# M865B.net
KiCad netlist of a schematic drawn in EAGLE
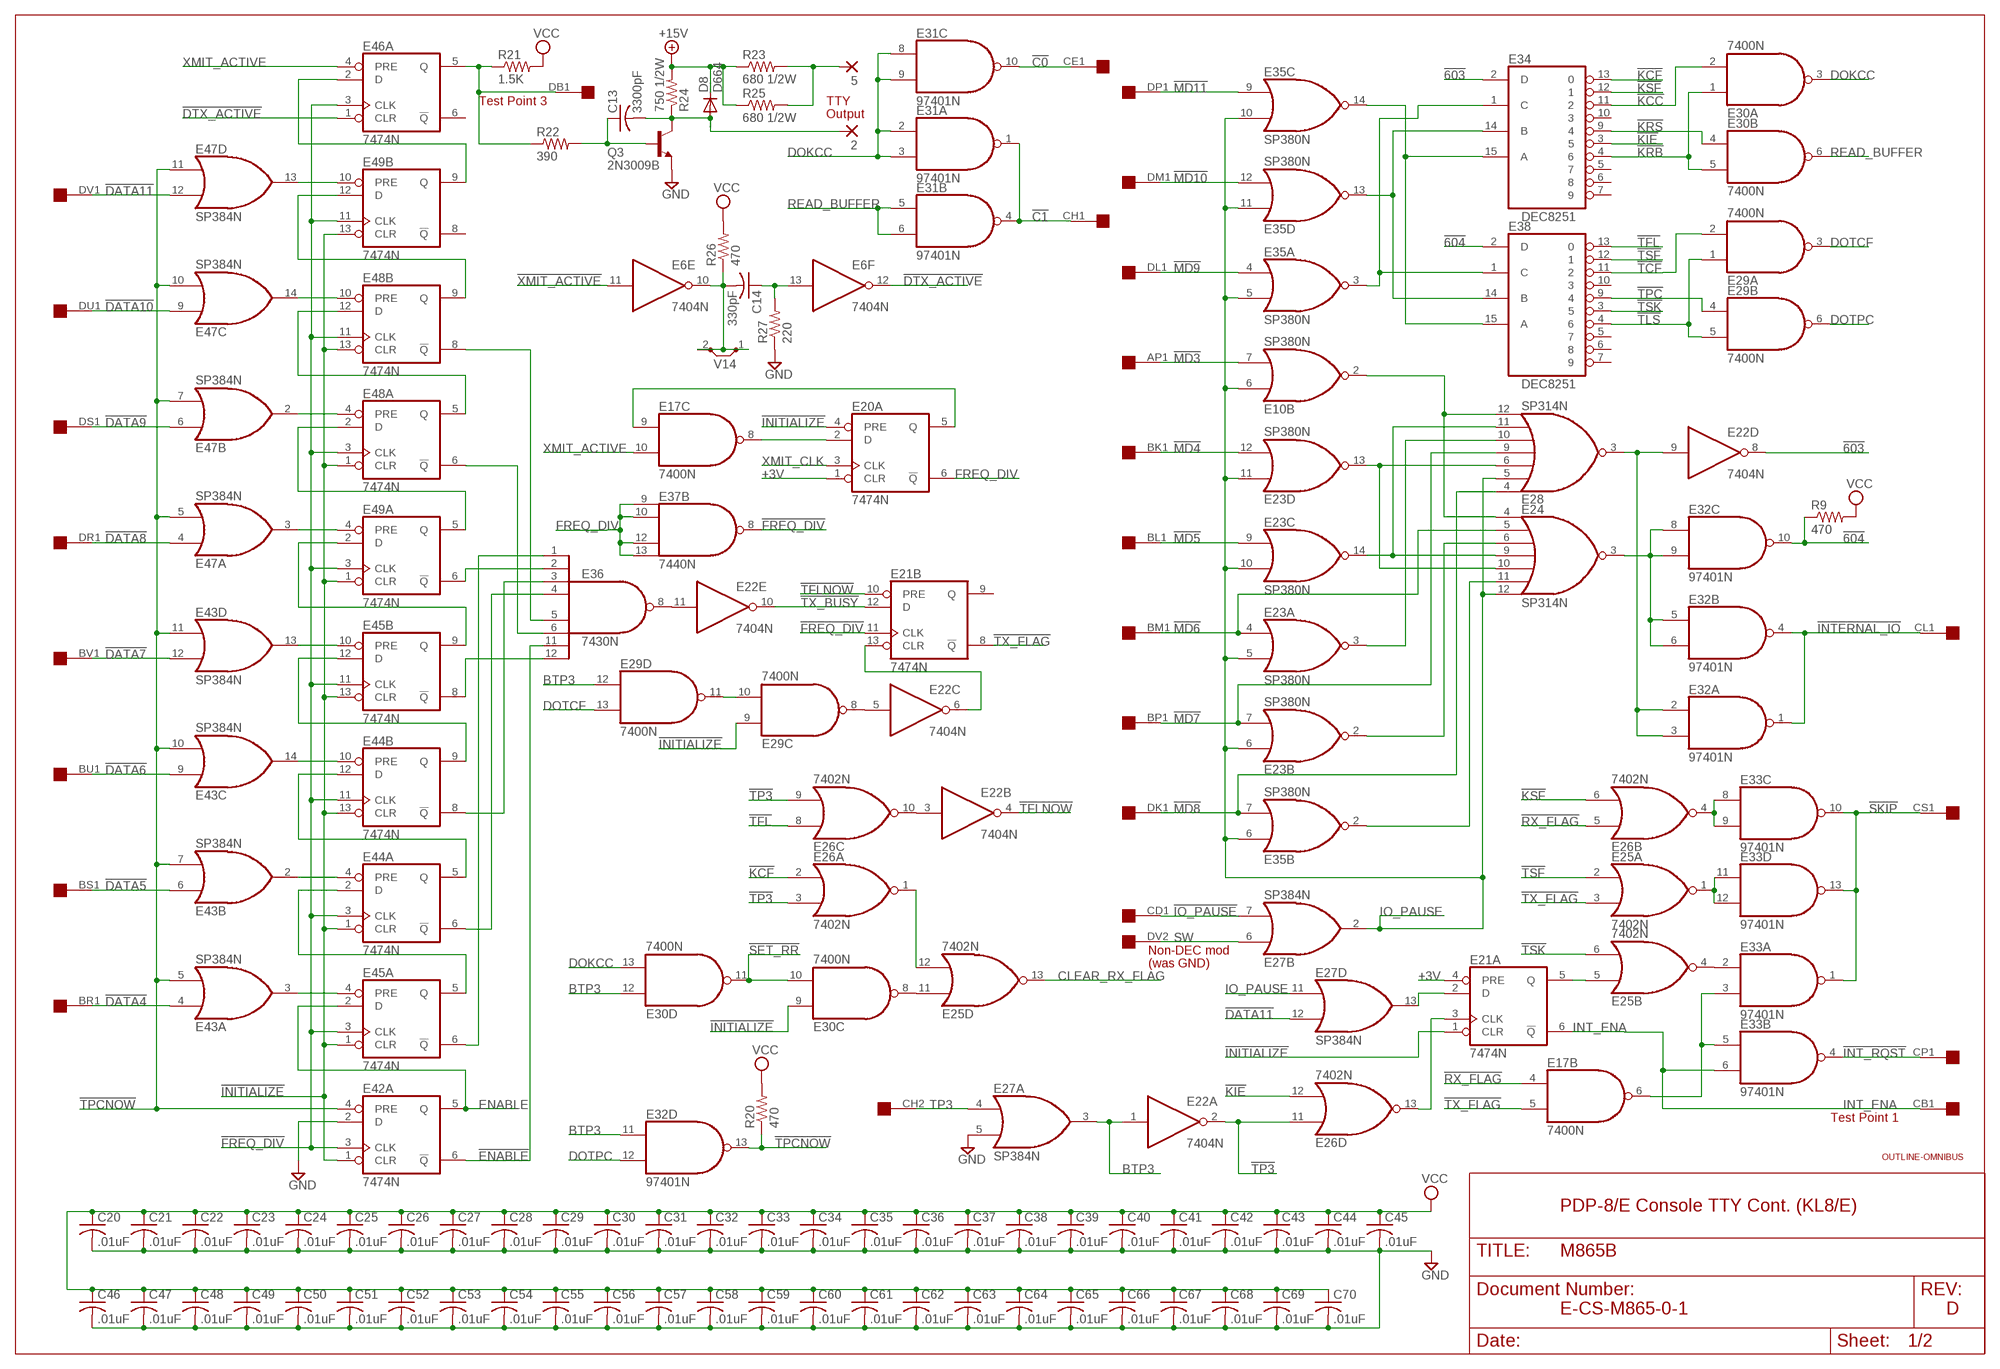
[diagram p0: schematic, sheet 1]
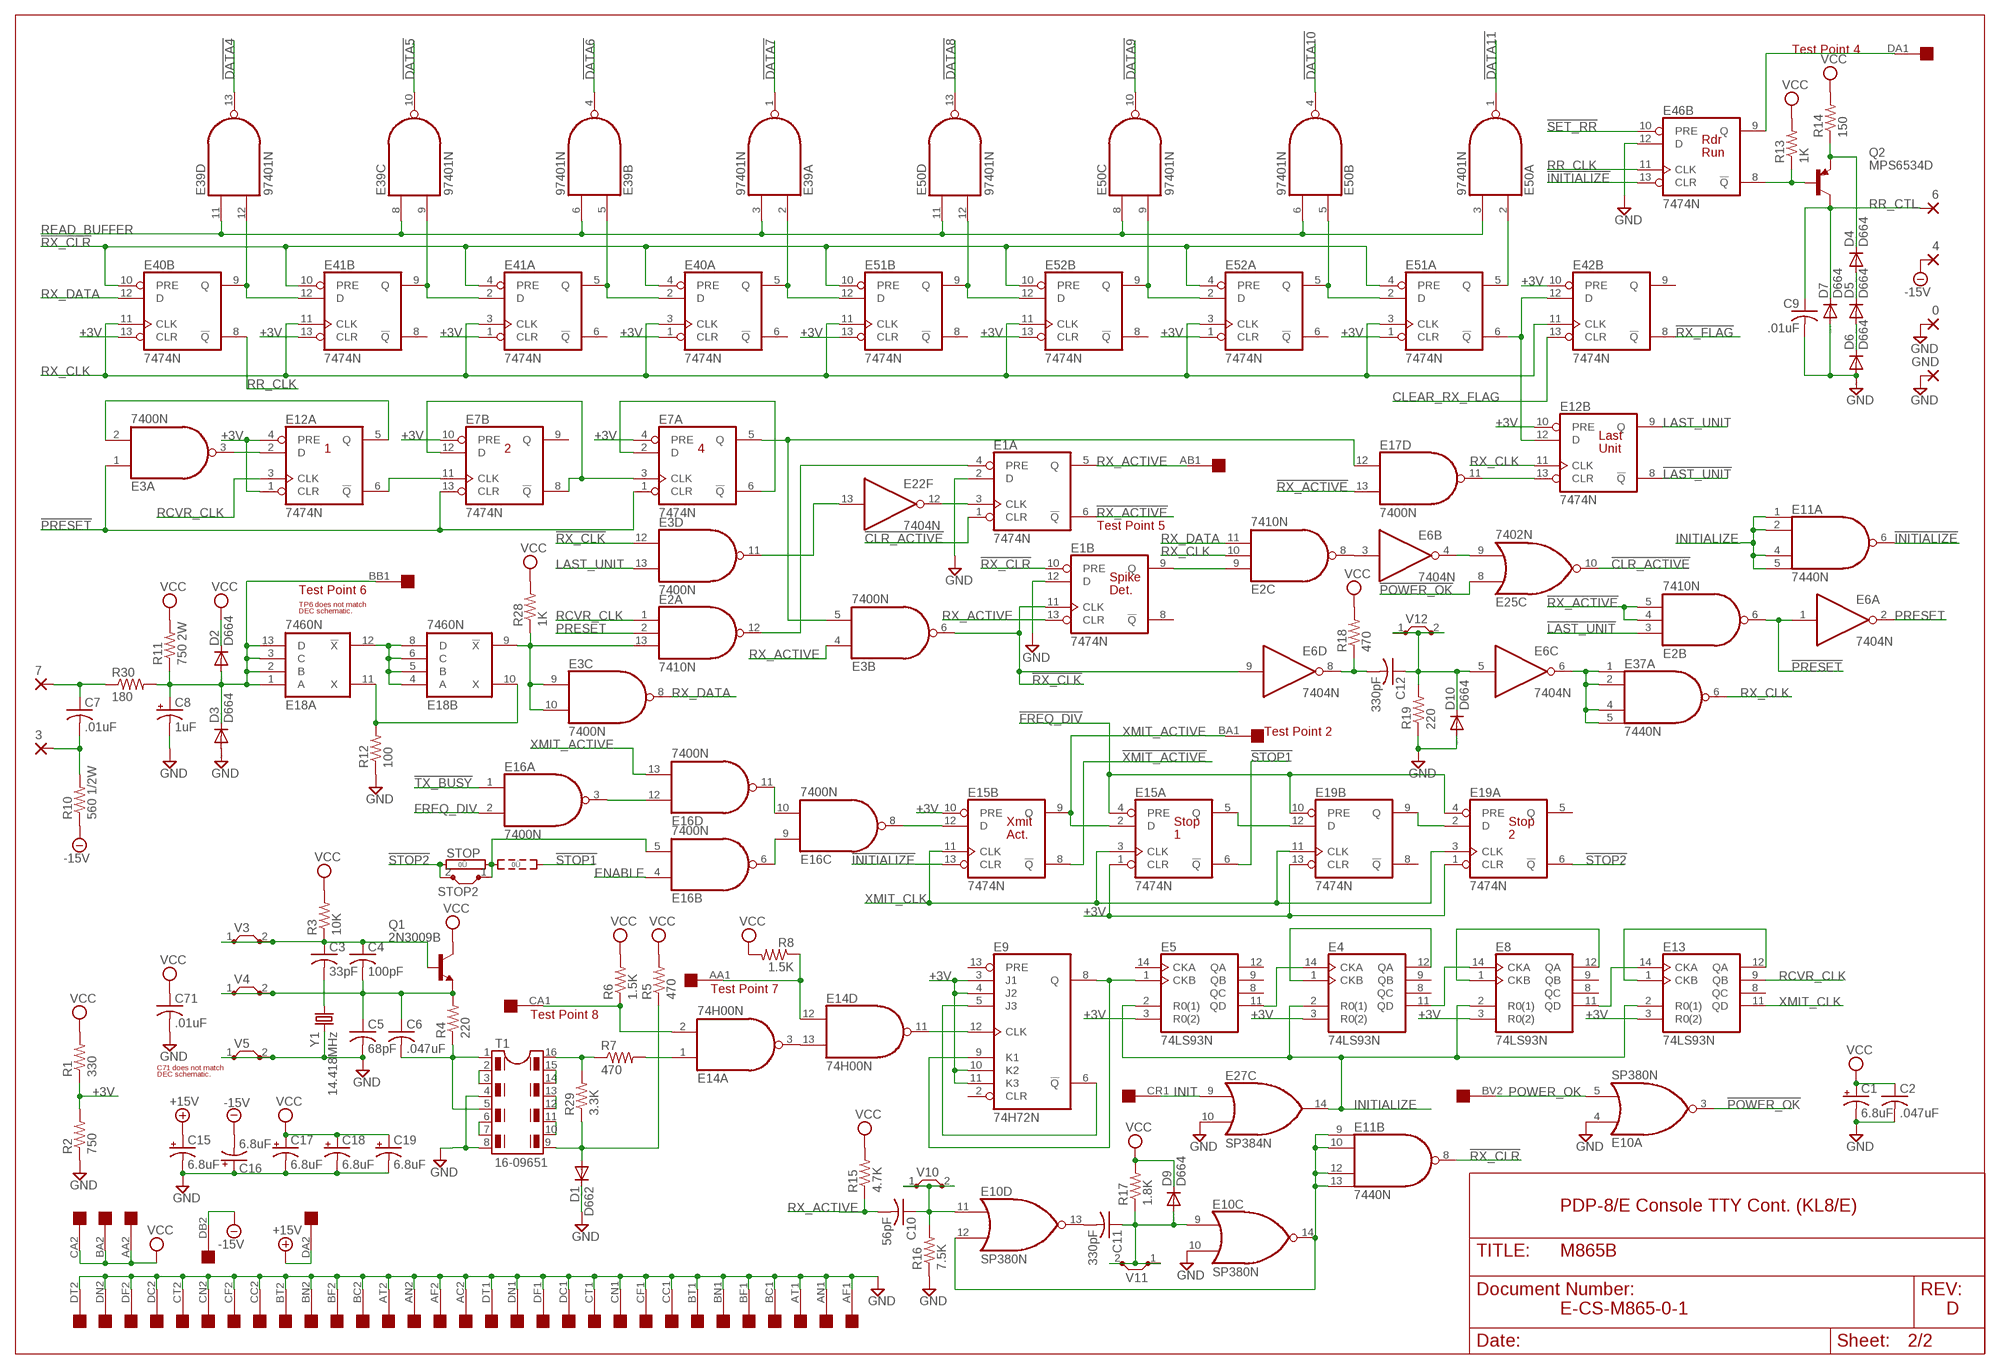
[diagram p1: schematic, sheet 2]

(export (version "E")
  (design (tool "Eeschema 10.0.6"))
  (components
    (comp (ref "0")
      (value "2,15/1,0")
      (footprint "eagle-import:2,15_1,0")
      (libsource (lib "eagle-import") (part "2,15/1,0"))
    )
    (comp (ref "3")
      (value "2,15/1,0")
      (footprint "eagle-import:2,15_1,0")
      (libsource (lib "eagle-import") (part "2,15/1,0"))
    )
    (comp (ref "4")
      (value "2,15/1,0")
      (footprint "eagle-import:2,15_1,0")
      (libsource (lib "eagle-import") (part "2,15/1,0"))
    )
    (comp (ref "6")
      (value "2,15/1,0")
      (footprint "eagle-import:2,15_1,0")
      (libsource (lib "eagle-import") (part "2,15/1,0"))
    )
    (comp (ref "7")
      (value "2,15/1,0")
      (footprint "eagle-import:2,15_1,0")
      (libsource (lib "eagle-import") (part "2,15/1,0"))
    )
    (comp (ref "C1")
      (value "6.8uF")
      (footprint "eagle-import:E12-8")
      (libsource (lib "eagle-import") (part "CPOL-USE20-8AXIAL"))
    )
    (comp (ref "C2")
      (value ".047uF")
      (footprint "eagle-import:C075-032X103")
      (libsource (lib "eagle-import") (part "C-US075-032X103"))
    )
    (comp (ref "C3")
      (value "33pF")
      (footprint "eagle-import:C050-025X075")
      (libsource (lib "eagle-import") (part "C-US050-025X075"))
    )
    (comp (ref "C4")
      (value "100pF")
      (footprint "eagle-import:C050-025X075")
      (libsource (lib "eagle-import") (part "C-US050-025X075"))
    )
    (comp (ref "C5")
      (value "68pF")
      (footprint "eagle-import:C050-025X075")
      (libsource (lib "eagle-import") (part "C-US050-025X075"))
    )
    (comp (ref "C6")
      (value ".047uF")
      (footprint "eagle-import:C075-032X103")
      (libsource (lib "eagle-import") (part "C-US075-032X103"))
    )
    (comp (ref "C7")
      (value ".01uF")
      (footprint "eagle-import:C050-025X075")
      (libsource (lib "eagle-import") (part "C-US050-025X075"))
    )
    (comp (ref "C8")
      (value "1uF")
      (footprint "eagle-import:E15-5")
      (libsource (lib "eagle-import") (part "CPOL-USE15-5AXIAL"))
    )
    (comp (ref "C9")
      (value ".01uF")
      (footprint "eagle-import:C050-025X075")
      (libsource (lib "eagle-import") (part "C-US050-025X075"))
    )
    (comp (ref "C10")
      (value "56pF")
      (footprint "eagle-import:C050-025X075")
      (libsource (lib "eagle-import") (part "C-US050-025X075"))
    )
    (comp (ref "C11")
      (value "330pF")
      (footprint "eagle-import:C050-025X075")
      (libsource (lib "eagle-import") (part "C-US050-025X075"))
    )
    (comp (ref "C12")
      (value "330pF")
      (footprint "eagle-import:C050-025X075")
      (libsource (lib "eagle-import") (part "C-US050-025X075"))
    )
    (comp (ref "C15")
      (value "6.8uF")
      (footprint "eagle-import:E12-8")
      (libsource (lib "eagle-import") (part "CPOL-USE20-8AXIAL"))
    )
    (comp (ref "C16")
      (value "6.8uF")
      (footprint "eagle-import:E12-8")
      (libsource (lib "eagle-import") (part "CPOL-USE20-8AXIAL"))
    )
    (comp (ref "C17")
      (value "6.8uF")
      (footprint "eagle-import:E12-8")
      (libsource (lib "eagle-import") (part "CPOL-USE20-8AXIAL"))
    )
    (comp (ref "C18")
      (value "6.8uF")
      (footprint "eagle-import:E12-8")
      (libsource (lib "eagle-import") (part "CPOL-USE20-8AXIAL"))
    )
    (comp (ref "C19")
      (value "6.8uF")
      (footprint "eagle-import:E12-8")
      (libsource (lib "eagle-import") (part "CPOL-USE20-8AXIAL"))
    )
    (comp (ref "C71")
      (value ".01uF")
      (footprint "eagle-import:C050-025X075")
      (libsource (lib "eagle-import") (part "C-US050-025X075"))
    )
    (comp (ref "D1")
      (value "D662")
      (footprint "eagle-import:DO35-10")
      (libsource (lib "eagle-import") (part "DIODE-DO35-10"))
    )
    (comp (ref "D2")
      (value "D664")
      (footprint "eagle-import:DO35-10")
      (libsource (lib "eagle-import") (part "DIODE-DO35-10"))
    )
    (comp (ref "D3")
      (value "D664")
      (footprint "eagle-import:DO35-10")
      (libsource (lib "eagle-import") (part "DIODE-DO35-10"))
    )
    (comp (ref "D4")
      (value "D664")
      (footprint "eagle-import:DO35-10")
      (libsource (lib "eagle-import") (part "DIODE-DO35-10"))
    )
    (comp (ref "D5")
      (value "D664")
      (footprint "eagle-import:DO35-10")
      (libsource (lib "eagle-import") (part "DIODE-DO35-10"))
    )
    (comp (ref "D6")
      (value "D664")
      (footprint "eagle-import:DO35-10")
      (libsource (lib "eagle-import") (part "DIODE-DO35-10"))
    )
    (comp (ref "D7")
      (value "D664")
      (footprint "eagle-import:DO35-10")
      (libsource (lib "eagle-import") (part "DIODE-DO35-10"))
    )
    (comp (ref "D9")
      (value "D664")
      (footprint "eagle-import:DO35-10")
      (libsource (lib "eagle-import") (part "DIODE-DO35-10"))
    )
    (comp (ref "D10")
      (value "D664")
      (footprint "eagle-import:DO35-10")
      (libsource (lib "eagle-import") (part "DIODE-DO35-10"))
    )
    (comp (ref "E1")
      (value "7474N")
      (footprint "eagle-import:DIL14")
      (libsource (lib "eagle-import") (part "7474NS"))
    )
    (comp (ref "E2")
      (value "7410N")
      (footprint "eagle-import:DIL14")
      (libsource (lib "eagle-import") (part "7410N"))
    )
    (comp (ref "E3")
      (value "7400N")
      (footprint "eagle-import:DIL14")
      (libsource (lib "eagle-import") (part "7400N"))
    )
    (comp (ref "E4")
      (value "74LS93N")
      (footprint "eagle-import:DIL14")
      (libsource (lib "eagle-import") (part "7493NLS"))
    )
    (comp (ref "E5")
      (value "74LS93N")
      (footprint "eagle-import:DIL14")
      (libsource (lib "eagle-import") (part "7493NLS"))
    )
    (comp (ref "E6")
      (value "7404N")
      (footprint "eagle-import:DIL14")
      (libsource (lib "eagle-import") (part "7404N"))
    )
    (comp (ref "E7")
      (value "7474N")
      (footprint "eagle-import:DIL14")
      (libsource (lib "eagle-import") (part "7474NS"))
    )
    (comp (ref "E8")
      (value "74LS93N")
      (footprint "eagle-import:DIL14")
      (libsource (lib "eagle-import") (part "7493NLS"))
    )
    (comp (ref "E9")
      (value "74H72N")
      (footprint "eagle-import:DIL14")
      (libsource (lib "eagle-import") (part "7472N"))
    )
    (comp (ref "E10")
      (value "SP380N")
      (footprint "eagle-import:DIL14")
      (libsource (lib "eagle-import") (part "SP380N"))
    )
    (comp (ref "E11")
      (value "7440N")
      (footprint "eagle-import:DIL14")
      (libsource (lib "eagle-import") (part "7440N"))
    )
    (comp (ref "E12")
      (value "7474N")
      (footprint "eagle-import:DIL14")
      (libsource (lib "eagle-import") (part "7474NS"))
    )
    (comp (ref "E13")
      (value "74LS93N")
      (footprint "eagle-import:DIL14")
      (libsource (lib "eagle-import") (part "7493NLS"))
    )
    (comp (ref "E14")
      (value "74H00N")
      (footprint "eagle-import:DIL14")
      (libsource (lib "eagle-import") (part "7400N"))
    )
    (comp (ref "E15")
      (value "7474N")
      (footprint "eagle-import:DIL14")
      (libsource (lib "eagle-import") (part "7474NS"))
    )
    (comp (ref "E16")
      (value "7400N")
      (footprint "eagle-import:DIL14")
      (libsource (lib "eagle-import") (part "7400N"))
    )
    (comp (ref "E17")
      (value "7400N")
      (footprint "eagle-import:DIL14")
      (libsource (lib "eagle-import") (part "7400N"))
    )
    (comp (ref "E18")
      (value "7460N")
      (footprint "eagle-import:DIL14")
      (libsource (lib "eagle-import") (part "7460N"))
    )
    (comp (ref "E19")
      (value "7474N")
      (footprint "eagle-import:DIL14")
      (libsource (lib "eagle-import") (part "7474NS"))
    )
    (comp (ref "E22")
      (value "7404N")
      (footprint "eagle-import:DIL14")
      (libsource (lib "eagle-import") (part "7404N"))
    )
    (comp (ref "E25")
      (value "7402N")
      (footprint "eagle-import:DIL14")
      (libsource (lib "eagle-import") (part "7402N"))
    )
    (comp (ref "E27")
      (value "SP384N")
      (footprint "eagle-import:DIL14")
      (libsource (lib "eagle-import") (part "SP384N"))
    )
    (comp (ref "E37")
      (value "7440N")
      (footprint "eagle-import:DIL14")
      (libsource (lib "eagle-import") (part "7440N"))
    )
    (comp (ref "E39")
      (value "97401N")
      (footprint "eagle-import:DIL14")
      (libsource (lib "eagle-import") (part "7401NLS"))
    )
    (comp (ref "E40")
      (value "7474N")
      (footprint "eagle-import:DIL14")
      (libsource (lib "eagle-import") (part "7474NS"))
    )
    (comp (ref "E41")
      (value "7474N")
      (footprint "eagle-import:DIL14")
      (libsource (lib "eagle-import") (part "7474NS"))
    )
    (comp (ref "E42")
      (value "7474N")
      (footprint "eagle-import:DIL14")
      (libsource (lib "eagle-import") (part "7474NS"))
    )
    (comp (ref "E46")
      (value "7474N")
      (footprint "eagle-import:DIL14")
      (libsource (lib "eagle-import") (part "7474NS"))
    )
    (comp (ref "E50")
      (value "97401N")
      (footprint "eagle-import:DIL14")
      (libsource (lib "eagle-import") (part "7401NLS"))
    )
    (comp (ref "E51")
      (value "7474N")
      (footprint "eagle-import:DIL14")
      (libsource (lib "eagle-import") (part "7474NS"))
    )
    (comp (ref "E52")
      (value "7474N")
      (footprint "eagle-import:DIL14")
      (libsource (lib "eagle-import") (part "7474NS"))
    )
    (comp (ref "GND")
      (value "2,15/1,0")
      (footprint "eagle-import:2,15_1,0")
      (libsource (lib "eagle-import") (part "2,15/1,0"))
    )
    (comp (ref "Q1")
      (value "2N3009B")
      (footprint "eagle-import:TO5")
      (libsource (lib "eagle-import") (part "-NPN-TO5"))
    )
    (comp (ref "Q2")
      (value "MPS6534D")
      (footprint "eagle-import:TO5")
      (libsource (lib "eagle-import") (part "-PNP-TO5"))
    )
    (comp (ref "R1")
      (value "330")
      (footprint "eagle-import:0207_10")
      (libsource (lib "eagle-import") (part "R-US_0207/10"))
    )
    (comp (ref "R2")
      (value "750")
      (footprint "eagle-import:0207_10")
      (libsource (lib "eagle-import") (part "R-US_0207/10"))
    )
    (comp (ref "R3")
      (value "10K")
      (footprint "eagle-import:0207_10")
      (libsource (lib "eagle-import") (part "R-US_0207/10"))
    )
    (comp (ref "R4")
      (value "220")
      (footprint "eagle-import:0207_10")
      (libsource (lib "eagle-import") (part "R-US_0207/10"))
    )
    (comp (ref "R5")
      (value "470")
      (footprint "eagle-import:0207_10")
      (libsource (lib "eagle-import") (part "R-US_0207/10"))
    )
    (comp (ref "R6")
      (value "1.5K")
      (footprint "eagle-import:0207_10")
      (libsource (lib "eagle-import") (part "R-US_0207/10"))
    )
    (comp (ref "R7")
      (value "470")
      (footprint "eagle-import:0207_10")
      (libsource (lib "eagle-import") (part "R-US_0207/10"))
    )
    (comp (ref "R8")
      (value "1.5K")
      (footprint "eagle-import:0207_10")
      (libsource (lib "eagle-import") (part "R-US_0207/10"))
    )
    (comp (ref "R10")
      (value "560 1/2W")
      (footprint "eagle-import:0411_15")
      (libsource (lib "eagle-import") (part "R-US_0411/15"))
    )
    (comp (ref "R11")
      (value "750 2W")
      (footprint "eagle-import:0818_25")
      (libsource (lib "eagle-import") (part "R-US_0818/25"))
    )
    (comp (ref "R12")
      (value "100")
      (footprint "eagle-import:0207_10")
      (libsource (lib "eagle-import") (part "R-US_0207/10"))
    )
    (comp (ref "R13")
      (value "1K")
      (footprint "eagle-import:0207_10")
      (libsource (lib "eagle-import") (part "R-US_0207/10"))
    )
    (comp (ref "R14")
      (value "150")
      (footprint "eagle-import:0207_10")
      (libsource (lib "eagle-import") (part "R-US_0207/10"))
    )
    (comp (ref "R15")
      (value "4.7K")
      (footprint "eagle-import:0207_10")
      (libsource (lib "eagle-import") (part "R-US_0207/10"))
    )
    (comp (ref "R16")
      (value "7.5K")
      (footprint "eagle-import:0207_10")
      (libsource (lib "eagle-import") (part "R-US_0207/10"))
    )
    (comp (ref "R17")
      (value "1.8K")
      (footprint "eagle-import:0207_10")
      (libsource (lib "eagle-import") (part "R-US_0207/10"))
    )
    (comp (ref "R18")
      (value "470")
      (footprint "eagle-import:0207_10")
      (libsource (lib "eagle-import") (part "R-US_0207/10"))
    )
    (comp (ref "R19")
      (value "220")
      (footprint "eagle-import:0207_10")
      (libsource (lib "eagle-import") (part "R-US_0207/10"))
    )
    (comp (ref "R28")
      (value "1K")
      (footprint "eagle-import:0207_10")
      (libsource (lib "eagle-import") (part "R-US_0207/10"))
    )
    (comp (ref "R29")
      (value "3.3K")
      (footprint "eagle-import:0207_10")
      (libsource (lib "eagle-import") (part "R-US_0207/10"))
    )
    (comp (ref "R30")
      (value "180")
      (footprint "eagle-import:0207_10")
      (libsource (lib "eagle-import") (part "R-US_0207/10"))
    )
    (comp (ref "STOP")
      (value "0R2")
      (footprint "eagle-import:0R2_10")
      (libsource (lib "eagle-import") (part "0R2"))
    )
    (comp (ref "STOP2")
      (value "J10MM")
      (footprint "eagle-import:10")
      (libsource (lib "eagle-import") (part "J10MM"))
    )
    (comp (ref "T1")
      (value "16-09651")
      (footprint "eagle-import:DIL16")
      (libsource (lib "eagle-import") (part "DIL16"))
    )
    (comp (ref "U$1")
      (value "QUAD")
      (footprint "eagle-import:EDGE-CON8")
      (libsource (lib "eagle-import") (part "QUAD"))
    )
    (comp (ref "V3")
      (value "J10MM")
      (footprint "eagle-import:10")
      (libsource (lib "eagle-import") (part "J10MM"))
    )
    (comp (ref "V4")
      (value "J10MM")
      (footprint "eagle-import:10")
      (libsource (lib "eagle-import") (part "J10MM"))
    )
    (comp (ref "V5")
      (value "J10MM")
      (footprint "eagle-import:10")
      (libsource (lib "eagle-import") (part "J10MM"))
    )
    (comp (ref "V10")
      (value "J10MM")
      (footprint "eagle-import:10")
      (libsource (lib "eagle-import") (part "J10MM"))
    )
    (comp (ref "V11")
      (value "J10MM")
      (footprint "eagle-import:10")
      (libsource (lib "eagle-import") (part "J10MM"))
    )
    (comp (ref "V12")
      (value "J10MM")
      (footprint "eagle-import:10")
      (libsource (lib "eagle-import") (part "J10MM"))
    )
    (comp (ref "Y1")
      (value "14.418MHz")
      (footprint "eagle-import:HC18U-H")
      (libsource (lib "eagle-import") (part "CRYSTALHC18U-H"))
    )
    (comp (ref "2")
      (value "2,15/1,0")
      (footprint "eagle-import:2,15_1,0")
      (libsource (lib "eagle-import") (part "2,15/1,0"))
    )
    (comp (ref "5")
      (value "2,15/1,0")
      (footprint "eagle-import:2,15_1,0")
      (libsource (lib "eagle-import") (part "2,15/1,0"))
    )
    (comp (ref "C13")
      (value "3300pF")
      (footprint "eagle-import:C102-043X133")
      (libsource (lib "eagle-import") (part "C-US102-043X133"))
    )
    (comp (ref "C14")
      (value "330pF")
      (footprint "eagle-import:C050-025X075")
      (libsource (lib "eagle-import") (part "C-US050-025X075"))
    )
    (comp (ref "C20")
      (value ".01uF")
      (footprint "eagle-import:C050-025X075")
      (libsource (lib "eagle-import") (part "C-US050-025X075"))
    )
    (comp (ref "C21")
      (value ".01uF")
      (footprint "eagle-import:C050-025X075")
      (libsource (lib "eagle-import") (part "C-US050-025X075"))
    )
    (comp (ref "C22")
      (value ".01uF")
      (footprint "eagle-import:C050-025X075")
      (libsource (lib "eagle-import") (part "C-US050-025X075"))
    )
    (comp (ref "C23")
      (value ".01uF")
      (footprint "eagle-import:C050-025X075")
      (libsource (lib "eagle-import") (part "C-US050-025X075"))
    )
    (comp (ref "C24")
      (value ".01uF")
      (footprint "eagle-import:C050-025X075")
      (libsource (lib "eagle-import") (part "C-US050-025X075"))
    )
    (comp (ref "C25")
      (value ".01uF")
      (footprint "eagle-import:C050-025X075")
      (libsource (lib "eagle-import") (part "C-US050-025X075"))
    )
    (comp (ref "C26")
      (value ".01uF")
      (footprint "eagle-import:C050-025X075")
      (libsource (lib "eagle-import") (part "C-US050-025X075"))
    )
    (comp (ref "C27")
      (value ".01uF")
      (footprint "eagle-import:C050-025X075")
      (libsource (lib "eagle-import") (part "C-US050-025X075"))
    )
    (comp (ref "C28")
      (value ".01uF")
      (footprint "eagle-import:C050-025X075")
      (libsource (lib "eagle-import") (part "C-US050-025X075"))
    )
    (comp (ref "C29")
      (value ".01uF")
      (footprint "eagle-import:C050-025X075")
      (libsource (lib "eagle-import") (part "C-US050-025X075"))
    )
    (comp (ref "C30")
      (value ".01uF")
      (footprint "eagle-import:C050-025X075")
      (libsource (lib "eagle-import") (part "C-US050-025X075"))
    )
    (comp (ref "C31")
      (value ".01uF")
      (footprint "eagle-import:C050-025X075")
      (libsource (lib "eagle-import") (part "C-US050-025X075"))
    )
    (comp (ref "C32")
      (value ".01uF")
      (footprint "eagle-import:C050-025X075")
      (libsource (lib "eagle-import") (part "C-US050-025X075"))
    )
    (comp (ref "C33")
      (value ".01uF")
      (footprint "eagle-import:C050-025X075")
      (libsource (lib "eagle-import") (part "C-US050-025X075"))
    )
    (comp (ref "C34")
      (value ".01uF")
      (footprint "eagle-import:C050-025X075")
      (libsource (lib "eagle-import") (part "C-US050-025X075"))
    )
    (comp (ref "C35")
      (value ".01uF")
      (footprint "eagle-import:C050-025X075")
      (libsource (lib "eagle-import") (part "C-US050-025X075"))
    )
    (comp (ref "C36")
      (value ".01uF")
      (footprint "eagle-import:C050-025X075")
      (libsource (lib "eagle-import") (part "C-US050-025X075"))
    )
    (comp (ref "C37")
      (value ".01uF")
      (footprint "eagle-import:C050-025X075")
      (libsource (lib "eagle-import") (part "C-US050-025X075"))
    )
    (comp (ref "C38")
      (value ".01uF")
      (footprint "eagle-import:C050-025X075")
      (libsource (lib "eagle-import") (part "C-US050-025X075"))
    )
    (comp (ref "C39")
      (value ".01uF")
      (footprint "eagle-import:C050-025X075")
      (libsource (lib "eagle-import") (part "C-US050-025X075"))
    )
    (comp (ref "C40")
      (value ".01uF")
      (footprint "eagle-import:C050-025X075")
      (libsource (lib "eagle-import") (part "C-US050-025X075"))
    )
    (comp (ref "C41")
      (value ".01uF")
      (footprint "eagle-import:C050-025X075")
      (libsource (lib "eagle-import") (part "C-US050-025X075"))
    )
    (comp (ref "C42")
      (value ".01uF")
      (footprint "eagle-import:C050-025X075")
      (libsource (lib "eagle-import") (part "C-US050-025X075"))
    )
    (comp (ref "C43")
      (value ".01uF")
      (footprint "eagle-import:C050-025X075")
      (libsource (lib "eagle-import") (part "C-US050-025X075"))
    )
    (comp (ref "C44")
      (value ".01uF")
      (footprint "eagle-import:C050-025X075")
      (libsource (lib "eagle-import") (part "C-US050-025X075"))
    )
    (comp (ref "C45")
      (value ".01uF")
      (footprint "eagle-import:C050-025X075")
      (libsource (lib "eagle-import") (part "C-US050-025X075"))
    )
    (comp (ref "C46")
      (value ".01uF")
      (footprint "eagle-import:C050-025X075")
      (libsource (lib "eagle-import") (part "C-US050-025X075"))
    )
    (comp (ref "C47")
      (value ".01uF")
      (footprint "eagle-import:C050-025X075")
      (libsource (lib "eagle-import") (part "C-US050-025X075"))
    )
    (comp (ref "C48")
      (value ".01uF")
      (footprint "eagle-import:C050-025X075")
      (libsource (lib "eagle-import") (part "C-US050-025X075"))
    )
    (comp (ref "C49")
      (value ".01uF")
      (footprint "eagle-import:C050-025X075")
      (libsource (lib "eagle-import") (part "C-US050-025X075"))
    )
    (comp (ref "C50")
      (value ".01uF")
      (footprint "eagle-import:C050-025X075")
      (libsource (lib "eagle-import") (part "C-US050-025X075"))
    )
    (comp (ref "C51")
      (value ".01uF")
      (footprint "eagle-import:C050-025X075")
      (libsource (lib "eagle-import") (part "C-US050-025X075"))
    )
    (comp (ref "C52")
      (value ".01uF")
      (footprint "eagle-import:C050-025X075")
      (libsource (lib "eagle-import") (part "C-US050-025X075"))
    )
    (comp (ref "C53")
      (value ".01uF")
      (footprint "eagle-import:C050-025X075")
      (libsource (lib "eagle-import") (part "C-US050-025X075"))
    )
    (comp (ref "C54")
      (value ".01uF")
      (footprint "eagle-import:C050-025X075")
      (libsource (lib "eagle-import") (part "C-US050-025X075"))
    )
    (comp (ref "C55")
      (value ".01uF")
      (footprint "eagle-import:C050-025X075")
      (libsource (lib "eagle-import") (part "C-US050-025X075"))
    )
    (comp (ref "C56")
      (value ".01uF")
      (footprint "eagle-import:C050-025X075")
      (libsource (lib "eagle-import") (part "C-US050-025X075"))
    )
    (comp (ref "C57")
      (value ".01uF")
      (footprint "eagle-import:C050-025X075")
      (libsource (lib "eagle-import") (part "C-US050-025X075"))
    )
    (comp (ref "C58")
      (value ".01uF")
      (footprint "eagle-import:C050-025X075")
      (libsource (lib "eagle-import") (part "C-US050-025X075"))
    )
    (comp (ref "C59")
      (value ".01uF")
      (footprint "eagle-import:C050-025X075")
      (libsource (lib "eagle-import") (part "C-US050-025X075"))
    )
    (comp (ref "C60")
      (value ".01uF")
      (footprint "eagle-import:C050-025X075")
      (libsource (lib "eagle-import") (part "C-US050-025X075"))
    )
    (comp (ref "C61")
      (value ".01uF")
      (footprint "eagle-import:C050-025X075")
      (libsource (lib "eagle-import") (part "C-US050-025X075"))
    )
    (comp (ref "C62")
      (value ".01uF")
      (footprint "eagle-import:C050-025X075")
      (libsource (lib "eagle-import") (part "C-US050-025X075"))
    )
    (comp (ref "C63")
      (value ".01uF")
      (footprint "eagle-import:C050-025X075")
      (libsource (lib "eagle-import") (part "C-US050-025X075"))
    )
    (comp (ref "C64")
      (value ".01uF")
      (footprint "eagle-import:C050-025X075")
      (libsource (lib "eagle-import") (part "C-US050-025X075"))
    )
    (comp (ref "C65")
      (value ".01uF")
      (footprint "eagle-import:C050-025X075")
      (libsource (lib "eagle-import") (part "C-US050-025X075"))
    )
    (comp (ref "C66")
      (value ".01uF")
      (footprint "eagle-import:C050-025X075")
      (libsource (lib "eagle-import") (part "C-US050-025X075"))
    )
    (comp (ref "C67")
      (value ".01uF")
      (footprint "eagle-import:C050-025X075")
      (libsource (lib "eagle-import") (part "C-US050-025X075"))
    )
    (comp (ref "C68")
      (value ".01uF")
      (footprint "eagle-import:C050-025X075")
      (libsource (lib "eagle-import") (part "C-US050-025X075"))
    )
    (comp (ref "C69")
      (value ".01uF")
      (footprint "eagle-import:C050-025X075")
      (libsource (lib "eagle-import") (part "C-US050-025X075"))
    )
    (comp (ref "C70")
      (value ".01uF")
      (footprint "eagle-import:C050-025X075")
      (libsource (lib "eagle-import") (part "C-US050-025X075"))
    )
    (comp (ref "D8")
      (value "D664")
      (footprint "eagle-import:DO35-10")
      (libsource (lib "eagle-import") (part "DIODE-DO35-10"))
    )
    (comp (ref "E20")
      (value "7474N")
      (footprint "eagle-import:DIL14")
      (libsource (lib "eagle-import") (part "7474NS"))
    )
    (comp (ref "E21")
      (value "7474N")
      (footprint "eagle-import:DIL14")
      (libsource (lib "eagle-import") (part "7474NS"))
    )
    (comp (ref "E23")
      (value "SP380N")
      (footprint "eagle-import:DIL14")
      (libsource (lib "eagle-import") (part "SP380N"))
    )
    (comp (ref "E24")
      (value "SP314N")
      (footprint "eagle-import:DIL14")
      (libsource (lib "eagle-import") (part "SP314N"))
    )
    (comp (ref "E26")
      (value "7402N")
      (footprint "eagle-import:DIL14")
      (libsource (lib "eagle-import") (part "7402N"))
    )
    (comp (ref "E28")
      (value "SP314N")
      (footprint "eagle-import:DIL14")
      (libsource (lib "eagle-import") (part "SP314N"))
    )
    (comp (ref "E29")
      (value "7400N")
      (footprint "eagle-import:DIL14")
      (libsource (lib "eagle-import") (part "7400N"))
    )
    (comp (ref "E30")
      (value "7400N")
      (footprint "eagle-import:DIL14")
      (libsource (lib "eagle-import") (part "7400N"))
    )
    (comp (ref "E31")
      (value "97401N")
      (footprint "eagle-import:DIL14")
      (libsource (lib "eagle-import") (part "7401NLS"))
    )
    (comp (ref "E32")
      (value "97401N")
      (footprint "eagle-import:DIL14")
      (libsource (lib "eagle-import") (part "7401NLS"))
    )
    (comp (ref "E33")
      (value "97401N")
      (footprint "eagle-import:DIL14")
      (libsource (lib "eagle-import") (part "7401NLS"))
    )
    (comp (ref "E34")
      (value "DEC8251")
      (footprint "eagle-import:DIL16")
      (libsource (lib "eagle-import") (part "DEC8251"))
    )
    (comp (ref "E35")
      (value "SP380N")
      (footprint "eagle-import:DIL14")
      (libsource (lib "eagle-import") (part "SP380N"))
    )
    (comp (ref "E36")
      (value "7430N")
      (footprint "eagle-import:DIL14")
      (libsource (lib "eagle-import") (part "7430N"))
    )
    (comp (ref "E38")
      (value "DEC8251")
      (footprint "eagle-import:DIL16")
      (libsource (lib "eagle-import") (part "DEC8251"))
    )
    (comp (ref "E43")
      (value "SP384N")
      (footprint "eagle-import:DIL14")
      (libsource (lib "eagle-import") (part "SP384N"))
    )
    (comp (ref "E44")
      (value "7474N")
      (footprint "eagle-import:DIL14")
      (libsource (lib "eagle-import") (part "7474NS"))
    )
    (comp (ref "E45")
      (value "7474N")
      (footprint "eagle-import:DIL14")
      (libsource (lib "eagle-import") (part "7474NS"))
    )
    (comp (ref "E47")
      (value "SP384N")
      (footprint "eagle-import:DIL14")
      (libsource (lib "eagle-import") (part "SP384N"))
    )
    (comp (ref "E48")
      (value "7474N")
      (footprint "eagle-import:DIL14")
      (libsource (lib "eagle-import") (part "7474NS"))
    )
    (comp (ref "E49")
      (value "7474N")
      (footprint "eagle-import:DIL14")
      (libsource (lib "eagle-import") (part "7474NS"))
    )
    (comp (ref "Q3")
      (value "2N3009B")
      (footprint "eagle-import:TO5")
      (libsource (lib "eagle-import") (part "-NPN-TO5"))
    )
    (comp (ref "R9")
      (value "470")
      (footprint "eagle-import:0207_10")
      (libsource (lib "eagle-import") (part "R-US_0207/10"))
    )
    (comp (ref "R20")
      (value "470")
      (footprint "eagle-import:0207_10")
      (libsource (lib "eagle-import") (part "R-US_0207/10"))
    )
    (comp (ref "R21")
      (value "1.5K")
      (footprint "eagle-import:0207_10")
      (libsource (lib "eagle-import") (part "R-US_0207/10"))
    )
    (comp (ref "R22")
      (value "390")
      (footprint "eagle-import:0207_10")
      (libsource (lib "eagle-import") (part "R-US_0207/10"))
    )
    (comp (ref "R23")
      (value "680 1/2W")
      (footprint "eagle-import:0411_15")
      (libsource (lib "eagle-import") (part "R-US_0411/15"))
    )
    (comp (ref "R24")
      (value "750 1/2W")
      (footprint "eagle-import:0411_15")
      (libsource (lib "eagle-import") (part "R-US_0411/15"))
    )
    (comp (ref "R25")
      (value "680 1/2W")
      (footprint "eagle-import:0411_15")
      (libsource (lib "eagle-import") (part "R-US_0411/15"))
    )
    (comp (ref "R26")
      (value "470")
      (footprint "eagle-import:0207_10")
      (libsource (lib "eagle-import") (part "R-US_0207/10"))
    )
    (comp (ref "R27")
      (value "220")
      (footprint "eagle-import:0207_10")
      (libsource (lib "eagle-import") (part "R-US_0207/10"))
    )
    (comp (ref "U$2")
      (value "OUTLINE-OMNIBUS")
      (footprint "eagle-import:OMNIBUS")
      (libsource (lib "eagle-import") (part "OUTLINE-OMNIBUS"))
    )
    (comp (ref "V14")
      (value "J10MM")
      (footprint "eagle-import:10")
      (libsource (lib "eagle-import") (part "J10MM"))
    )
  )
  (nets
    (net (code "1") (name "+3V") (class "Default")
      (node (ref "E12") (pin "1") (pinfunction "CLR_1") (pintype "input"))
      (node (ref "E12") (pin "10") (pinfunction "PRE_10") (pintype "input"))
      (node (ref "E12") (pin "4") (pinfunction "PRE_4") (pintype "input"))
      (node (ref "E13") (pin "3") (pinfunction "R0(2)_3") (pintype "input"))
      (node (ref "E15") (pin "1") (pinfunction "CLR_1") (pintype "input"))
      (node (ref "E15") (pin "10") (pinfunction "PRE_10") (pintype "input"))
      (node (ref "E19") (pin "1") (pinfunction "CLR_1") (pintype "input"))
      (node (ref "E19") (pin "13") (pinfunction "CLR_13") (pintype "input"))
      (node (ref "E20") (pin "1") (pinfunction "CLR_1") (pintype "input"))
      (node (ref "E21") (pin "4") (pinfunction "PRE_4") (pintype "input"))
      (node (ref "E4") (pin "3") (pinfunction "R0(2)_3") (pintype "input"))
      (node (ref "E40") (pin "1") (pinfunction "CLR_1") (pintype "input"))
      (node (ref "E40") (pin "13") (pinfunction "CLR_13") (pintype "input"))
      (node (ref "E41") (pin "1") (pinfunction "CLR_1") (pintype "input"))
      (node (ref "E41") (pin "13") (pinfunction "CLR_13") (pintype "input"))
      (node (ref "E42") (pin "10") (pinfunction "PRE_10") (pintype "input"))
      (node (ref "E5") (pin "3") (pinfunction "R0(2)_3") (pintype "input"))
      (node (ref "E51") (pin "1") (pinfunction "CLR_1") (pintype "input"))
      (node (ref "E51") (pin "13") (pinfunction "CLR_13") (pintype "input"))
      (node (ref "E52") (pin "1") (pinfunction "CLR_1") (pintype "input"))
      (node (ref "E52") (pin "13") (pinfunction "CLR_13") (pintype "input"))
      (node (ref "E7") (pin "10") (pinfunction "PRE_10") (pintype "input"))
      (node (ref "E7") (pin "4") (pinfunction "PRE_4") (pintype "input"))
      (node (ref "E8") (pin "3") (pinfunction "R0(2)_3") (pintype "input"))
      (node (ref "E9") (pin "10") (pinfunction "K2_10") (pintype "input"))
      (node (ref "E9") (pin "11") (pinfunction "K3_11") (pintype "input"))
      (node (ref "E9") (pin "3") (pinfunction "J1_3") (pintype "input"))
      (node (ref "E9") (pin "4") (pinfunction "J2_4") (pintype "input"))
      (node (ref "R1") (pin "1") (pinfunction "1_1") (pintype "passive"))
      (node (ref "R2") (pin "2") (pinfunction "2_2") (pintype "passive"))
    )
    (net (code "2") (name "+15V") (class "Default")
      (node (ref "C15") (pin "+") (pinfunction "+_+") (pintype "passive"))
      (node (ref "D8") (pin "C") (pinfunction "C_C") (pintype "passive"))
      (node (ref "R23") (pin "1") (pinfunction "1_1") (pintype "passive"))
      (node (ref "R24") (pin "2") (pinfunction "2_2") (pintype "passive"))
      (node (ref "R25") (pin "1") (pinfunction "1_1") (pintype "passive"))
      (node (ref "U$1") (pin "DA2") (pinfunction "1_DA2") (pintype "bidirectional"))
    )
    (net (code "3") (name "-15V") (class "Default")
      (node (ref "4") (pin "1") (pinfunction "P_1") (pintype "passive"))
      (node (ref "C16") (pin "-") (pinfunction "-_-") (pintype "passive"))
      (node (ref "R10") (pin "1") (pinfunction "1_1") (pintype "passive"))
      (node (ref "U$1") (pin "DB2") (pinfunction "1_DB2") (pintype "bidirectional"))
    )
    (net (code "4") (name "BTP3") (class "Default")
      (node (ref "E22") (pin "1") (pinfunction "I_1") (pintype "input"))
      (node (ref "E27") (pin "3") (pinfunction "O_3") (pintype "output"))
      (node (ref "E29") (pin "12") (pinfunction "I0_12") (pintype "input"))
      (node (ref "E30") (pin "12") (pinfunction "I0_12") (pintype "input"))
      (node (ref "E32") (pin "11") (pinfunction "I0_11") (pintype "input"))
    )
    (net (code "5") (name "CLEAR_RX_FLAG") (class "Default")
      (node (ref "E25") (pin "13") (pinfunction "O_13") (pintype "output"))
      (node (ref "E42") (pin "13") (pinfunction "CLR_13") (pintype "input"))
    )
    (net (code "6") (name "DOKCC") (class "Default")
      (node (ref "E30") (pin "13") (pinfunction "I1_13") (pintype "input"))
      (node (ref "E30") (pin "3") (pinfunction "O_3") (pintype "output"))
      (node (ref "E31") (pin "2") (pinfunction "I0_2") (pintype "input"))
      (node (ref "E31") (pin "3") (pinfunction "I1_3") (pintype "input"))
      (node (ref "E31") (pin "8") (pinfunction "I0_8") (pintype "input"))
      (node (ref "E31") (pin "9") (pinfunction "I1_9") (pintype "input"))
    )
    (net (code "7") (name "DOTCF") (class "Default")
      (node (ref "E29") (pin "13") (pinfunction "I1_13") (pintype "input"))
      (node (ref "E29") (pin "3") (pinfunction "O_3") (pintype "output"))
    )
    (net (code "8") (name "DOTPC") (class "Default")
      (node (ref "E29") (pin "6") (pinfunction "O_6") (pintype "output"))
      (node (ref "E32") (pin "12") (pinfunction "I1_12") (pintype "input"))
    )
    (net (code "9") (name "ENABLE") (class "Default")
      (node (ref "E16") (pin "4") (pinfunction "I0_4") (pintype "input"))
      (node (ref "E42") (pin "5") (pinfunction "Q_5") (pintype "output"))
      (node (ref "E45") (pin "2") (pinfunction "D_2") (pintype "input"))
    )
    (net (code "10") (name "FREQ_DIV") (class "Default")
      (node (ref "E16") (pin "2") (pinfunction "I1_2") (pintype "input"))
      (node (ref "E20") (pin "6") (pinfunction "~{Q}_6") (pintype "output"))
      (node (ref "E37") (pin "10") (pinfunction "I1_10") (pintype "input"))
      (node (ref "E37") (pin "12") (pinfunction "I2_12") (pintype "input"))
      (node (ref "E37") (pin "13") (pinfunction "I3_13") (pintype "input"))
      (node (ref "E37") (pin "9") (pinfunction "I0_9") (pintype "input"))
    )
    (net (code "11") (name "GND") (class "Default")
      (node (ref "0") (pin "1") (pinfunction "P_1") (pintype "passive"))
      (node (ref "C1") (pin "-") (pinfunction "-_-") (pintype "passive"))
      (node (ref "C15") (pin "-") (pinfunction "-_-") (pintype "passive"))
      (node (ref "C16") (pin "+") (pinfunction "+_+") (pintype "passive"))
      (node (ref "C17") (pin "-") (pinfunction "-_-") (pintype "passive"))
      (node (ref "C18") (pin "-") (pinfunction "-_-") (pintype "passive"))
      (node (ref "C19") (pin "-") (pinfunction "-_-") (pintype "passive"))
      (node (ref "C2") (pin "2") (pinfunction "2_2") (pintype "passive"))
      (node (ref "C20") (pin "2") (pinfunction "2_2") (pintype "passive"))
      (node (ref "C21") (pin "2") (pinfunction "2_2") (pintype "passive"))
      (node (ref "C22") (pin "2") (pinfunction "2_2") (pintype "passive"))
      (node (ref "C23") (pin "2") (pinfunction "2_2") (pintype "passive"))
      (node (ref "C24") (pin "2") (pinfunction "2_2") (pintype "passive"))
      (node (ref "C25") (pin "2") (pinfunction "2_2") (pintype "passive"))
      (node (ref "C26") (pin "2") (pinfunction "2_2") (pintype "passive"))
      (node (ref "C27") (pin "2") (pinfunction "2_2") (pintype "passive"))
      (node (ref "C28") (pin "2") (pinfunction "2_2") (pintype "passive"))
      (node (ref "C29") (pin "2") (pinfunction "2_2") (pintype "passive"))
      (node (ref "C30") (pin "2") (pinfunction "2_2") (pintype "passive"))
      (node (ref "C31") (pin "2") (pinfunction "2_2") (pintype "passive"))
      (node (ref "C32") (pin "2") (pinfunction "2_2") (pintype "passive"))
      (node (ref "C33") (pin "2") (pinfunction "2_2") (pintype "passive"))
      (node (ref "C34") (pin "2") (pinfunction "2_2") (pintype "passive"))
      (node (ref "C35") (pin "2") (pinfunction "2_2") (pintype "passive"))
      (node (ref "C36") (pin "2") (pinfunction "2_2") (pintype "passive"))
      (node (ref "C37") (pin "2") (pinfunction "2_2") (pintype "passive"))
      (node (ref "C38") (pin "2") (pinfunction "2_2") (pintype "passive"))
      (node (ref "C39") (pin "2") (pinfunction "2_2") (pintype "passive"))
      (node (ref "C40") (pin "2") (pinfunction "2_2") (pintype "passive"))
      (node (ref "C41") (pin "2") (pinfunction "2_2") (pintype "passive"))
      (node (ref "C42") (pin "2") (pinfunction "2_2") (pintype "passive"))
      (node (ref "C43") (pin "2") (pinfunction "2_2") (pintype "passive"))
      (node (ref "C44") (pin "2") (pinfunction "2_2") (pintype "passive"))
      (node (ref "C45") (pin "2") (pinfunction "2_2") (pintype "passive"))
      (node (ref "C46") (pin "2") (pinfunction "2_2") (pintype "passive"))
      (node (ref "C47") (pin "2") (pinfunction "2_2") (pintype "passive"))
      (node (ref "C48") (pin "2") (pinfunction "2_2") (pintype "passive"))
      (node (ref "C49") (pin "2") (pinfunction "2_2") (pintype "passive"))
      (node (ref "C5") (pin "2") (pinfunction "2_2") (pintype "passive"))
      (node (ref "C50") (pin "2") (pinfunction "2_2") (pintype "passive"))
      (node (ref "C51") (pin "2") (pinfunction "2_2") (pintype "passive"))
      (node (ref "C52") (pin "2") (pinfunction "2_2") (pintype "passive"))
      (node (ref "C53") (pin "2") (pinfunction "2_2") (pintype "passive"))
      (node (ref "C54") (pin "2") (pinfunction "2_2") (pintype "passive"))
      (node (ref "C55") (pin "2") (pinfunction "2_2") (pintype "passive"))
      (node (ref "C56") (pin "2") (pinfunction "2_2") (pintype "passive"))
      (node (ref "C57") (pin "2") (pinfunction "2_2") (pintype "passive"))
      (node (ref "C58") (pin "2") (pinfunction "2_2") (pintype "passive"))
      (node (ref "C59") (pin "2") (pinfunction "2_2") (pintype "passive"))
      (node (ref "C60") (pin "2") (pinfunction "2_2") (pintype "passive"))
      (node (ref "C61") (pin "2") (pinfunction "2_2") (pintype "passive"))
      (node (ref "C62") (pin "2") (pinfunction "2_2") (pintype "passive"))
      (node (ref "C63") (pin "2") (pinfunction "2_2") (pintype "passive"))
      (node (ref "C64") (pin "2") (pinfunction "2_2") (pintype "passive"))
      (node (ref "C65") (pin "2") (pinfunction "2_2") (pintype "passive"))
      (node (ref "C66") (pin "2") (pinfunction "2_2") (pintype "passive"))
      (node (ref "C67") (pin "2") (pinfunction "2_2") (pintype "passive"))
      (node (ref "C68") (pin "2") (pinfunction "2_2") (pintype "passive"))
      (node (ref "C69") (pin "2") (pinfunction "2_2") (pintype "passive"))
      (node (ref "C70") (pin "2") (pinfunction "2_2") (pintype "passive"))
      (node (ref "C71") (pin "2") (pinfunction "2_2") (pintype "passive"))
      (node (ref "C8") (pin "-") (pinfunction "-_-") (pintype "passive"))
      (node (ref "C9") (pin "2") (pinfunction "2_2") (pintype "passive"))
      (node (ref "D1") (pin "C") (pinfunction "C_C") (pintype "passive"))
      (node (ref "D10") (pin "A") (pinfunction "A_A") (pintype "passive"))
      (node (ref "D3") (pin "A") (pinfunction "A_A") (pintype "passive"))
      (node (ref "D6") (pin "A") (pinfunction "A_A") (pintype "passive"))
      (node (ref "D7") (pin "A") (pinfunction "A_A") (pintype "passive"))
      (node (ref "E1") (pin "12") (pinfunction "D_12") (pintype "input"))
      (node (ref "E1") (pin "2") (pinfunction "D_2") (pintype "input"))
      (node (ref "E10") (pin "10") (pinfunction "I1_10") (pintype "input"))
      (node (ref "E10") (pin "4") (pinfunction "I0_4") (pintype "input"))
      (node (ref "E27") (pin "10") (pinfunction "I1_10") (pintype "input"))
      (node (ref "E27") (pin "5") (pinfunction "I1_5") (pintype "input"))
      (node (ref "E42") (pin "2") (pinfunction "D_2") (pintype "input"))
      (node (ref "E46") (pin "12") (pinfunction "D_12") (pintype "input"))
      (node (ref "GND") (pin "1") (pinfunction "P_1") (pintype "passive"))
      (node (ref "Q3") (pin "1") (pinfunction "E_1") (pintype "passive"))
      (node (ref "R12") (pin "1") (pinfunction "1_1") (pintype "passive"))
      (node (ref "R16") (pin "1") (pinfunction "1_1") (pintype "passive"))
      (node (ref "R19") (pin "1") (pinfunction "1_1") (pintype "passive"))
      (node (ref "R2") (pin "1") (pinfunction "1_1") (pintype "passive"))
      (node (ref "R27") (pin "1") (pinfunction "1_1") (pintype "passive"))
      (node (ref "T1") (pin "4") (pinfunction "4_4") (pintype "passive"))
      (node (ref "T1") (pin "8") (pinfunction "8_8") (pintype "passive"))
      (node (ref "U$1") (pin "AC2") (pinfunction "1_AC2") (pintype "bidirectional"))
      (node (ref "U$1") (pin "AF1") (pinfunction "1_AF1") (pintype "bidirectional"))
      (node (ref "U$1") (pin "AF2") (pinfunction "1_AF2") (pintype "bidirectional"))
      (node (ref "U$1") (pin "AN1") (pinfunction "1_AN1") (pintype "bidirectional"))
      (node (ref "U$1") (pin "AN2") (pinfunction "1_AN2") (pintype "bidirectional"))
      (node (ref "U$1") (pin "AT1") (pinfunction "1_AT1") (pintype "bidirectional"))
      (node (ref "U$1") (pin "AT2") (pinfunction "1_AT2") (pintype "bidirectional"))
      (node (ref "U$1") (pin "BC1") (pinfunction "1_BC1") (pintype "bidirectional"))
      (node (ref "U$1") (pin "BC2") (pinfunction "1_BC2") (pintype "bidirectional"))
      (node (ref "U$1") (pin "BF1") (pinfunction "1_BF1") (pintype "bidirectional"))
      (node (ref "U$1") (pin "BF2") (pinfunction "1_BF2") (pintype "bidirectional"))
      (node (ref "U$1") (pin "BN1") (pinfunction "1_BN1") (pintype "bidirectional"))
      (node (ref "U$1") (pin "BN2") (pinfunction "1_BN2") (pintype "bidirectional"))
      (node (ref "U$1") (pin "BT1") (pinfunction "1_BT1") (pintype "bidirectional"))
      (node (ref "U$1") (pin "BT2") (pinfunction "1_BT2") (pintype "bidirectional"))
      (node (ref "U$1") (pin "CC1") (pinfunction "1_CC1") (pintype "bidirectional"))
      (node (ref "U$1") (pin "CC2") (pinfunction "1_CC2") (pintype "bidirectional"))
      (node (ref "U$1") (pin "CF1") (pinfunction "1_CF1") (pintype "bidirectional"))
      (node (ref "U$1") (pin "CF2") (pinfunction "1_CF2") (pintype "bidirectional"))
      (node (ref "U$1") (pin "CN1") (pinfunction "1_CN1") (pintype "bidirectional"))
      (node (ref "U$1") (pin "CN2") (pinfunction "1_CN2") (pintype "bidirectional"))
      (node (ref "U$1") (pin "CT1") (pinfunction "1_CT1") (pintype "bidirectional"))
      (node (ref "U$1") (pin "CT2") (pinfunction "1_CT2") (pintype "bidirectional"))
      (node (ref "U$1") (pin "DC1") (pinfunction "1_DC1") (pintype "bidirectional"))
      (node (ref "U$1") (pin "DC2") (pinfunction "1_DC2") (pintype "bidirectional"))
      (node (ref "U$1") (pin "DF1") (pinfunction "1_DF1") (pintype "bidirectional"))
      (node (ref "U$1") (pin "DF2") (pinfunction "1_DF2") (pintype "bidirectional"))
      (node (ref "U$1") (pin "DN1") (pinfunction "1_DN1") (pintype "bidirectional"))
      (node (ref "U$1") (pin "DN2") (pinfunction "1_DN2") (pintype "bidirectional"))
      (node (ref "U$1") (pin "DT1") (pinfunction "1_DT1") (pintype "bidirectional"))
      (node (ref "U$1") (pin "DT2") (pinfunction "1_DT2") (pintype "bidirectional"))
      (node (ref "V5") (pin "1") (pinfunction "1_1") (pintype "passive"))
      (node (ref "V5") (pin "2") (pinfunction "2_2") (pintype "passive"))
      (node (ref "Y1") (pin "2") (pinfunction "2_2") (pintype "passive"))
    )
    (net (code "12") (name "INIT") (class "Default")
      (node (ref "E27") (pin "9") (pinfunction "I0_9") (pintype "input"))
      (node (ref "U$1") (pin "CR1") (pinfunction "1_CR1") (pintype "bidirectional"))
    )
    (net (code "13") (name "INITIALIZE") (class "Default")
      (node (ref "E11") (pin "1") (pinfunction "I0_1") (pintype "input"))
      (node (ref "E11") (pin "2") (pinfunction "I1_2") (pintype "input"))
      (node (ref "E11") (pin "4") (pinfunction "I2_4") (pintype "input"))
      (node (ref "E11") (pin "5") (pinfunction "I3_5") (pintype "input"))
      (node (ref "E13") (pin "2") (pinfunction "R0(1)_2") (pintype "input"))
      (node (ref "E27") (pin "14") (pinfunction "O_14") (pintype "output"))
      (node (ref "E4") (pin "2") (pinfunction "R0(1)_2") (pintype "input"))
      (node (ref "E5") (pin "2") (pinfunction "R0(1)_2") (pintype "input"))
      (node (ref "E8") (pin "2") (pinfunction "R0(1)_2") (pintype "input"))
    )
    (net (code "14") (name "INT_ENA") (class "Default")
      (node (ref "E21") (pin "6") (pinfunction "~{Q}_6") (pintype "output"))
      (node (ref "E33") (pin "6") (pinfunction "I1_6") (pintype "input"))
      (node (ref "U$1") (pin "CB1") (pinfunction "1_CB1") (pintype "bidirectional"))
    )
    (net (code "15") (name "IO_PAUSE") (class "Default")
      (node (ref "E10") (pin "6") (pinfunction "I0_6") (pintype "input"))
      (node (ref "E23") (pin "10") (pinfunction "I1_10") (pintype "input"))
      (node (ref "E23") (pin "11") (pinfunction "I0_11") (pintype "input"))
      (node (ref "E23") (pin "5") (pinfunction "I1_5") (pintype "input"))
      (node (ref "E23") (pin "6") (pinfunction "I0_6") (pintype "input"))
      (node (ref "E24") (pin "12") (pinfunction "I6_12") (pintype "input"))
      (node (ref "E27") (pin "11") (pinfunction "I0_11") (pintype "input"))
      (node (ref "E27") (pin "2") (pinfunction "O_2") (pintype "output"))
      (node (ref "E28") (pin "5") (pinfunction "I1_5") (pintype "input"))
      (node (ref "E35") (pin "10") (pinfunction "I1_10") (pintype "input"))
      (node (ref "E35") (pin "11") (pinfunction "I0_11") (pintype "input"))
      (node (ref "E35") (pin "5") (pinfunction "I1_5") (pintype "input"))
      (node (ref "E35") (pin "6") (pinfunction "I0_6") (pintype "input"))
    )
    (net (code "16") (name "LAST_UNIT") (class "Default")
      (node (ref "E12") (pin "9") (pinfunction "Q_9") (pintype "output"))
      (node (ref "E3") (pin "13") (pinfunction "I1_13") (pintype "input"))
    )
    (net (code "17") (name "Net-(2-P)") (class "Default")
      (node (ref "2") (pin "1") (pinfunction "P_1") (pintype "passive"))
      (node (ref "C13") (pin "2") (pinfunction "2_2") (pintype "passive"))
      (node (ref "D8") (pin "A") (pinfunction "A_A") (pintype "passive"))
      (node (ref "Q3") (pin "3") (pinfunction "C_3") (pintype "passive"))
      (node (ref "R24") (pin "1") (pinfunction "1_1") (pintype "passive"))
    )
    (net (code "18") (name "Net-(3-P)") (class "Default")
      (node (ref "3") (pin "1") (pinfunction "P_1") (pintype "passive"))
      (node (ref "C7") (pin "2") (pinfunction "2_2") (pintype "passive"))
      (node (ref "R10") (pin "2") (pinfunction "2_2") (pintype "passive"))
    )
    (net (code "19") (name "Net-(5-P)") (class "Default")
      (node (ref "5") (pin "1") (pinfunction "P_1") (pintype "passive"))
      (node (ref "R23") (pin "2") (pinfunction "2_2") (pintype "passive"))
      (node (ref "R25") (pin "2") (pinfunction "2_2") (pintype "passive"))
    )
    (net (code "20") (name "Net-(7-P)") (class "Default")
      (node (ref "7") (pin "1") (pinfunction "P_1") (pintype "passive"))
      (node (ref "C7") (pin "1") (pinfunction "1_1") (pintype "passive"))
      (node (ref "R30") (pin "1") (pinfunction "1_1") (pintype "passive"))
    )
    (net (code "21") (name "Net-(C3-Pad2)") (class "Default")
      (node (ref "C3") (pin "2") (pinfunction "2_2") (pintype "passive"))
      (node (ref "Y1") (pin "1") (pinfunction "1_1") (pintype "passive"))
    )
    (net (code "22") (name "Net-(C6-Pad2)") (class "Default")
      (node (ref "C6") (pin "2") (pinfunction "2_2") (pintype "passive"))
      (node (ref "R4") (pin "1") (pinfunction "1_1") (pintype "passive"))
      (node (ref "T1") (pin "1") (pinfunction "1_1") (pintype "passive"))
      (node (ref "T1") (pin "5") (pinfunction "5_5") (pintype "passive"))
    )
    (net (code "23") (name "Net-(D1-PadA)") (class "Default")
      (node (ref "D1") (pin "A") (pinfunction "A_A") (pintype "passive"))
      (node (ref "R29") (pin "1") (pinfunction "1_1") (pintype "passive"))
      (node (ref "R5") (pin "1") (pinfunction "1_1") (pintype "passive"))
      (node (ref "T1") (pin "9") (pinfunction "9_9") (pintype "passive"))
    )
    (net (code "24") (name "Net-(D4-PadA)") (class "Default")
      (node (ref "D4") (pin "A") (pinfunction "A_A") (pintype "passive"))
      (node (ref "D5") (pin "C") (pinfunction "C_C") (pintype "passive"))
    )
    (net (code "25") (name "Net-(D5-PadA)") (class "Default")
      (node (ref "D5") (pin "A") (pinfunction "A_A") (pintype "passive"))
      (node (ref "D6") (pin "C") (pinfunction "C_C") (pintype "passive"))
    )
    (net (code "26") (name "Net-(E1A-CLK)") (class "Default")
      (node (ref "E1") (pin "3") (pinfunction "CLK_3") (pintype "input"))
      (node (ref "E22") (pin "12") (pinfunction "O_12") (pintype "output"))
    )
    (net (code "27") (name "Net-(E1A-PRE)") (class "Default")
      (node (ref "E1") (pin "4") (pinfunction "PRE_4") (pintype "input"))
      (node (ref "E2") (pin "12") (pinfunction "O_12") (pintype "output"))
    )
    (net (code "28") (name "Net-(E1B-Q)") (class "Default")
      (node (ref "E1") (pin "9") (pinfunction "Q_9") (pintype "output"))
      (node (ref "E2") (pin "9") (pinfunction "I0_9") (pintype "input"))
    )
    (net (code "29") (name "Net-(E2C-O)") (class "Default")
      (node (ref "E2") (pin "8") (pinfunction "O_8") (pintype "output"))
      (node (ref "E6") (pin "3") (pinfunction "I_3") (pintype "input"))
    )
    (net (code "30") (name "Net-(E4A-CKA)") (class "Default")
      (node (ref "E4") (pin "14") (pinfunction "CKA_14") (pintype "input"))
      (node (ref "E5") (pin "11") (pinfunction "QD_11") (pintype "output"))
    )
    (net (code "31") (name "Net-(E4A-CKB)") (class "Default")
      (node (ref "E4") (pin "1") (pinfunction "CKB_1") (pintype "input"))
      (node (ref "E4") (pin "12") (pinfunction "QA_12") (pintype "output"))
    )
    (net (code "32") (name "Net-(E4A-QD)") (class "Default")
      (node (ref "E4") (pin "11") (pinfunction "QD_11") (pintype "output"))
      (node (ref "E8") (pin "14") (pinfunction "CKA_14") (pintype "input"))
    )
    (net (code "33") (name "Net-(E5A-CKB)") (class "Default")
      (node (ref "E5") (pin "1") (pinfunction "CKB_1") (pintype "input"))
      (node (ref "E9") (pin "8") (pinfunction "Q_8") (pintype "output"))
      (node (ref "E9") (pin "9") (pinfunction "K1_9") (pintype "input"))
    )
    (net (code "34") (name "Net-(E6C-I)") (class "Default")
      (node (ref "C12") (pin "1") (pinfunction "1_1") (pintype "passive"))
      (node (ref "D10") (pin "C") (pinfunction "C_C") (pintype "passive"))
      (node (ref "E6") (pin "5") (pinfunction "I_5") (pintype "input"))
      (node (ref "R19") (pin "2") (pinfunction "2_2") (pintype "passive"))
      (node (ref "V12") (pin "1") (pinfunction "1_1") (pintype "passive"))
      (node (ref "V12") (pin "2") (pinfunction "2_2") (pintype "passive"))
    )
    (net (code "35") (name "Net-(E6D-O)") (class "Default")
      (node (ref "C12") (pin "2") (pinfunction "2_2") (pintype "passive"))
      (node (ref "E6") (pin "8") (pinfunction "O_8") (pintype "output"))
      (node (ref "R18") (pin "1") (pinfunction "1_1") (pintype "passive"))
    )
    (net (code "36") (name "Net-(E6E-O)") (class "Default")
      (node (ref "C14") (pin "2") (pinfunction "2_2") (pintype "passive"))
      (node (ref "E6") (pin "10") (pinfunction "O_10") (pintype "output"))
      (node (ref "R26") (pin "1") (pinfunction "1_1") (pintype "passive"))
      (node (ref "V14") (pin "1") (pinfunction "1_1") (pintype "passive"))
      (node (ref "V14") (pin "2") (pinfunction "2_2") (pintype "passive"))
    )
    (net (code "37") (name "Net-(E6F-I)") (class "Default")
      (node (ref "C14") (pin "1") (pinfunction "1_1") (pintype "passive"))
      (node (ref "E6") (pin "13") (pinfunction "I_13") (pintype "input"))
      (node (ref "R27") (pin "2") (pinfunction "2_2") (pintype "passive"))
    )
    (net (code "38") (name "Net-(E7A-CLK)") (class "Default")
      (node (ref "E7") (pin "12") (pinfunction "D_12") (pintype "input"))
      (node (ref "E7") (pin "3") (pinfunction "CLK_3") (pintype "input"))
      (node (ref "E7") (pin "8") (pinfunction "~{Q}_8") (pintype "output"))
    )
    (net (code "39") (name "Net-(E7A-D)") (class "Default")
      (node (ref "E7") (pin "2") (pinfunction "D_2") (pintype "input"))
      (node (ref "E7") (pin "6") (pinfunction "~{Q}_6") (pintype "output"))
    )
    (net (code "40") (name "Net-(E8A-CKB)") (class "Default")
      (node (ref "E8") (pin "1") (pinfunction "CKB_1") (pintype "input"))
      (node (ref "E8") (pin "12") (pinfunction "QA_12") (pintype "output"))
    )
    (net (code "41") (name "Net-(E9A-J3)") (class "Default")
      (node (ref "E9") (pin "5") (pinfunction "J3_5") (pintype "input"))
      (node (ref "E9") (pin "6") (pinfunction "~{Q}_6") (pintype "output"))
    )
    (net (code "42") (name "Net-(E10B-O)") (class "Default")
      (node (ref "E10") (pin "2") (pinfunction "O_2") (pintype "output"))
      (node (ref "E24") (pin "4") (pinfunction "I0_4") (pintype "input"))
      (node (ref "E28") (pin "12") (pinfunction "I6_12") (pintype "input"))
    )
    (net (code "43") (name "Net-(E10C-I0)") (class "Default")
      (node (ref "C11") (pin "1") (pinfunction "1_1") (pintype "passive"))
      (node (ref "D9") (pin "A") (pinfunction "A_A") (pintype "passive"))
      (node (ref "E10") (pin "9") (pinfunction "I0_9") (pintype "input"))
      (node (ref "R17") (pin "1") (pinfunction "1_1") (pintype "passive"))
      (node (ref "V11") (pin "1") (pinfunction "1_1") (pintype "passive"))
      (node (ref "V11") (pin "2") (pinfunction "2_2") (pintype "passive"))
    )
    (net (code "44") (name "Net-(E10C-O)") (class "Default")
      (node (ref "E10") (pin "12") (pinfunction "I1_12") (pintype "input"))
      (node (ref "E10") (pin "14") (pinfunction "O_14") (pintype "output"))
      (node (ref "E11") (pin "10") (pinfunction "I1_10") (pintype "input"))
      (node (ref "E11") (pin "12") (pinfunction "I2_12") (pintype "input"))
      (node (ref "E11") (pin "13") (pinfunction "I3_13") (pintype "input"))
      (node (ref "E11") (pin "9") (pinfunction "I0_9") (pintype "input"))
    )
    (net (code "45") (name "Net-(E10D-I0)") (class "Default")
      (node (ref "C10") (pin "1") (pinfunction "1_1") (pintype "passive"))
      (node (ref "E10") (pin "11") (pinfunction "I0_11") (pintype "input"))
      (node (ref "R16") (pin "2") (pinfunction "2_2") (pintype "passive"))
      (node (ref "V10") (pin "1") (pinfunction "1_1") (pintype "passive"))
      (node (ref "V10") (pin "2") (pinfunction "2_2") (pintype "passive"))
    )
    (net (code "46") (name "Net-(E10D-O)") (class "Default")
      (node (ref "C11") (pin "2") (pinfunction "2_2") (pintype "passive"))
      (node (ref "E10") (pin "13") (pinfunction "O_13") (pintype "output"))
    )
    (net (code "47") (name "Net-(E12A-D)") (class "Default")
      (node (ref "E12") (pin "2") (pinfunction "D_2") (pintype "input"))
      (node (ref "E3") (pin "3") (pinfunction "O_3") (pintype "output"))
    )
    (net (code "48") (name "Net-(E12A-Q)") (class "Default")
      (node (ref "E12") (pin "5") (pinfunction "Q_5") (pintype "output"))
      (node (ref "E3") (pin "2") (pinfunction "I1_2") (pintype "input"))
    )
    (net (code "49") (name "Net-(E12A-~{Q})") (class "Default")
      (node (ref "E12") (pin "6") (pinfunction "~{Q}_6") (pintype "output"))
      (node (ref "E7") (pin "11") (pinfunction "CLK_11") (pintype "input"))
    )
    (net (code "50") (name "Net-(E12B-CLR)") (class "Default")
      (node (ref "E12") (pin "13") (pinfunction "CLR_13") (pintype "input"))
      (node (ref "E17") (pin "11") (pinfunction "O_11") (pintype "output"))
    )
    (net (code "51") (name "Net-(E12B-D)") (class "Default")
      (node (ref "E12") (pin "12") (pinfunction "D_12") (pintype "input"))
      (node (ref "E42") (pin "12") (pinfunction "D_12") (pintype "input"))
      (node (ref "E51") (pin "6") (pinfunction "~{Q}_6") (pintype "output"))
    )
    (net (code "52") (name "Net-(E13A-CKA)") (class "Default")
      (node (ref "E13") (pin "14") (pinfunction "CKA_14") (pintype "input"))
      (node (ref "E8") (pin "11") (pinfunction "QD_11") (pintype "output"))
    )
    (net (code "53") (name "Net-(E13A-CKB)") (class "Default")
      (node (ref "E13") (pin "1") (pinfunction "CKB_1") (pintype "input"))
      (node (ref "E13") (pin "12") (pinfunction "QA_12") (pintype "output"))
    )
    (net (code "54") (name "Net-(E14A-I0)") (class "Default")
      (node (ref "E14") (pin "1") (pinfunction "I0_1") (pintype "input"))
      (node (ref "R7") (pin "2") (pinfunction "2_2") (pintype "passive"))
    )
    (net (code "55") (name "Net-(E14A-I1)") (class "Default")
      (node (ref "E14") (pin "2") (pinfunction "I1_2") (pintype "input"))
      (node (ref "R6") (pin "1") (pinfunction "1_1") (pintype "passive"))
      (node (ref "U$1") (pin "CA1") (pinfunction "1_CA1") (pintype "bidirectional"))
    )
    (net (code "56") (name "Net-(E14A-O)") (class "Default")
      (node (ref "E14") (pin "13") (pinfunction "I1_13") (pintype "input"))
      (node (ref "E14") (pin "3") (pinfunction "O_3") (pintype "output"))
    )
    (net (code "57") (name "Net-(E14D-I0)") (class "Default")
      (node (ref "E14") (pin "12") (pinfunction "I0_12") (pintype "input"))
      (node (ref "R8") (pin "1") (pinfunction "1_1") (pintype "passive"))
      (node (ref "U$1") (pin "AA1") (pinfunction "1_AA1") (pintype "bidirectional"))
    )
    (net (code "58") (name "Net-(E14D-O)") (class "Default")
      (node (ref "E14") (pin "11") (pinfunction "O_11") (pintype "output"))
      (node (ref "E9") (pin "12") (pinfunction "CLK_12") (pintype "input"))
    )
    (net (code "59") (name "Net-(E15A-Q)") (class "Default")
      (node (ref "E15") (pin "5") (pinfunction "Q_5") (pintype "output"))
      (node (ref "E19") (pin "12") (pinfunction "D_12") (pintype "input"))
    )
    (net (code "60") (name "Net-(E15B-D)") (class "Default")
      (node (ref "E15") (pin "12") (pinfunction "D_12") (pintype "input"))
      (node (ref "E16") (pin "8") (pinfunction "O_8") (pintype "output"))
    )
    (net (code "61") (name "Net-(E16A-O)") (class "Default")
      (node (ref "E16") (pin "12") (pinfunction "I0_12") (pintype "input"))
      (node (ref "E16") (pin "3") (pinfunction "O_3") (pintype "output"))
    )
    (net (code "62") (name "Net-(E16B-I1)") (class "Default")
      (node (ref "E16") (pin "5") (pinfunction "I1_5") (pintype "input"))
      (node (ref "STOP") (pin "2") (pinfunction "2_2") (pintype "passive"))
      (node (ref "STOP2") (pin "1") (pinfunction "1_1") (pintype "passive"))
    )
    (net (code "63") (name "Net-(E16B-O)") (class "Default")
      (node (ref "E16") (pin "6") (pinfunction "O_6") (pintype "output"))
      (node (ref "E16") (pin "9") (pinfunction "I0_9") (pintype "input"))
    )
    (net (code "64") (name "Net-(E16C-I1)") (class "Default")
      (node (ref "E16") (pin "10") (pinfunction "I1_10") (pintype "input"))
      (node (ref "E16") (pin "11") (pinfunction "O_11") (pintype "output"))
    )
    (net (code "65") (name "Net-(E17B-O)") (class "Default")
      (node (ref "E17") (pin "6") (pinfunction "O_6") (pintype "output"))
      (node (ref "E33") (pin "3") (pinfunction "I1_3") (pintype "input"))
      (node (ref "E33") (pin "5") (pinfunction "I0_5") (pintype "input"))
    )
    (net (code "66") (name "Net-(E17C-I0)") (class "Default")
      (node (ref "E17") (pin "9") (pinfunction "I0_9") (pintype "input"))
      (node (ref "E20") (pin "5") (pinfunction "Q_5") (pintype "output"))
    )
    (net (code "67") (name "Net-(E17C-O)") (class "Default")
      (node (ref "E17") (pin "8") (pinfunction "O_8") (pintype "output"))
      (node (ref "E20") (pin "2") (pinfunction "D_2") (pintype "input"))
    )
    (net (code "68") (name "Net-(E17D-I0)") (class "Default")
      (node (ref "E17") (pin "12") (pinfunction "I0_12") (pintype "input"))
      (node (ref "E3") (pin "5") (pinfunction "I1_5") (pintype "input"))
      (node (ref "E7") (pin "5") (pinfunction "Q_5") (pintype "output"))
    )
    (net (code "69") (name "Net-(E18A-A)") (class "Default")
      (node (ref "C8") (pin "+") (pinfunction "+_+") (pintype "passive"))
      (node (ref "D2") (pin "A") (pinfunction "A_A") (pintype "passive"))
      (node (ref "D3") (pin "C") (pinfunction "C_C") (pintype "passive"))
      (node (ref "E18") (pin "1") (pinfunction "A_1") (pintype "input"))
      (node (ref "E18") (pin "13") (pinfunction "D_13") (pintype "input"))
      (node (ref "E18") (pin "2") (pinfunction "B_2") (pintype "input"))
      (node (ref "E18") (pin "3") (pinfunction "C_3") (pintype "input"))
      (node (ref "R11") (pin "1") (pinfunction "1_1") (pintype "passive"))
      (node (ref "R30") (pin "2") (pinfunction "2_2") (pintype "passive"))
      (node (ref "U$1") (pin "BB1") (pinfunction "1_BB1") (pintype "bidirectional"))
    )
    (net (code "70") (name "Net-(E18A-X)") (class "Default")
      (node (ref "E18") (pin "10") (pinfunction "X_10") (pintype "output"))
      (node (ref "E18") (pin "11") (pinfunction "X_11") (pintype "output"))
      (node (ref "R12") (pin "2") (pinfunction "2_2") (pintype "passive"))
    )
    (net (code "71") (name "Net-(E18A-~{X})") (class "Default")
      (node (ref "E18") (pin "12") (pinfunction "~{X}_12") (pintype "output"))
      (node (ref "E18") (pin "4") (pinfunction "A_4") (pintype "input"))
      (node (ref "E18") (pin "5") (pinfunction "B_5") (pintype "input"))
      (node (ref "E18") (pin "6") (pinfunction "C_6") (pintype "input"))
      (node (ref "E18") (pin "8") (pinfunction "D_8") (pintype "input"))
    )
    (net (code "72") (name "Net-(E18B-~{X})") (class "Default")
      (node (ref "E18") (pin "9") (pinfunction "~{X}_9") (pintype "output"))
      (node (ref "E2") (pin "13") (pinfunction "I2_13") (pintype "input"))
      (node (ref "E3") (pin "10") (pinfunction "I1_10") (pintype "input"))
      (node (ref "E3") (pin "9") (pinfunction "I0_9") (pintype "input"))
      (node (ref "R28") (pin "1") (pinfunction "1_1") (pintype "passive"))
    )
    (net (code "73") (name "Net-(E19A-D)") (class "Default")
      (node (ref "E19") (pin "2") (pinfunction "D_2") (pintype "input"))
      (node (ref "E19") (pin "9") (pinfunction "Q_9") (pintype "output"))
    )
    (net (code "74") (name "Net-(E21A-CLK)") (class "Default")
      (node (ref "E21") (pin "3") (pinfunction "CLK_3") (pintype "input"))
      (node (ref "E26") (pin "13") (pinfunction "O_13") (pintype "output"))
    )
    (net (code "75") (name "Net-(E21A-D)") (class "Default")
      (node (ref "E21") (pin "2") (pinfunction "D_2") (pintype "input"))
      (node (ref "E27") (pin "13") (pinfunction "O_13") (pintype "output"))
    )
    (net (code "76") (name "Net-(E21A-Q)") (class "Default")
      (node (ref "E21") (pin "5") (pinfunction "Q_5") (pintype "output"))
      (node (ref "E25") (pin "5") (pinfunction "I0_5") (pintype "input"))
    )
    (net (code "77") (name "Net-(E21B-CLR)") (class "Default")
      (node (ref "E21") (pin "13") (pinfunction "CLR_13") (pintype "input"))
      (node (ref "E22") (pin "6") (pinfunction "O_6") (pintype "output"))
    )
    (net (code "78") (name "Net-(E22B-I)") (class "Default")
      (node (ref "E22") (pin "3") (pinfunction "I_3") (pintype "input"))
      (node (ref "E26") (pin "10") (pinfunction "O_10") (pintype "output"))
    )
    (net (code "79") (name "Net-(E22C-I)") (class "Default")
      (node (ref "E22") (pin "5") (pinfunction "I_5") (pintype "input"))
      (node (ref "E29") (pin "8") (pinfunction "O_8") (pintype "output"))
    )
    (net (code "80") (name "Net-(E22D-I)") (class "Default")
      (node (ref "E22") (pin "9") (pinfunction "I_9") (pintype "input"))
      (node (ref "E28") (pin "3") (pinfunction "O_3") (pintype "output"))
      (node (ref "E32") (pin "2") (pinfunction "I0_2") (pintype "input"))
      (node (ref "E32") (pin "3") (pinfunction "I1_3") (pintype "input"))
    )
    (net (code "81") (name "Net-(E22E-I)") (class "Default")
      (node (ref "E22") (pin "11") (pinfunction "I_11") (pintype "input"))
      (node (ref "E36") (pin "8") (pinfunction "O_8") (pintype "output"))
    )
    (net (code "82") (name "Net-(E22F-I)") (class "Default")
      (node (ref "E22") (pin "13") (pinfunction "I_13") (pintype "input"))
      (node (ref "E3") (pin "11") (pinfunction "O_11") (pintype "output"))
    )
    (net (code "83") (name "Net-(E23A-O)") (class "Default")
      (node (ref "E23") (pin "3") (pinfunction "O_3") (pintype "output"))
      (node (ref "E28") (pin "10") (pinfunction "I4_10") (pintype "input"))
    )
    (net (code "84") (name "Net-(E23B-O)") (class "Default")
      (node (ref "E23") (pin "2") (pinfunction "O_2") (pintype "output"))
      (node (ref "E24") (pin "6") (pinfunction "I2_6") (pintype "input"))
    )
    (net (code "85") (name "Net-(E23C-O)") (class "Default")
      (node (ref "E23") (pin "14") (pinfunction "O_14") (pintype "output"))
      (node (ref "E24") (pin "9") (pinfunction "I3_9") (pintype "input"))
      (node (ref "E28") (pin "11") (pinfunction "I5_11") (pintype "input"))
    )
    (net (code "86") (name "Net-(E23D-O)") (class "Default")
      (node (ref "E23") (pin "13") (pinfunction "O_13") (pintype "output"))
      (node (ref "E24") (pin "10") (pinfunction "I4_10") (pintype "input"))
      (node (ref "E28") (pin "6") (pinfunction "I2_6") (pintype "input"))
    )
    (net (code "87") (name "Net-(E24A-I5)") (class "Default")
      (node (ref "E24") (pin "11") (pinfunction "I5_11") (pintype "input"))
      (node (ref "E35") (pin "2") (pinfunction "O_2") (pintype "output"))
    )
    (net (code "88") (name "Net-(E24A-O)") (class "Default")
      (node (ref "E24") (pin "3") (pinfunction "O_3") (pintype "output"))
      (node (ref "E32") (pin "5") (pinfunction "I0_5") (pintype "input"))
      (node (ref "E32") (pin "6") (pinfunction "I1_6") (pintype "input"))
      (node (ref "E32") (pin "8") (pinfunction "I0_8") (pintype "input"))
      (node (ref "E32") (pin "9") (pinfunction "I1_9") (pintype "input"))
    )
    (net (code "89") (name "Net-(E25A-O)") (class "Default")
      (node (ref "E25") (pin "1") (pinfunction "O_1") (pintype "output"))
      (node (ref "E33") (pin "11") (pinfunction "I0_11") (pintype "input"))
      (node (ref "E33") (pin "12") (pinfunction "I1_12") (pintype "input"))
    )
    (net (code "90") (name "Net-(E25B-O)") (class "Default")
      (node (ref "E25") (pin "4") (pinfunction "O_4") (pintype "output"))
      (node (ref "E33") (pin "2") (pinfunction "I0_2") (pintype "input"))
    )
    (net (code "91") (name "Net-(E25C-I1)") (class "Default")
      (node (ref "E25") (pin "9") (pinfunction "I1_9") (pintype "input"))
      (node (ref "E6") (pin "4") (pinfunction "O_4") (pintype "output"))
    )
    (net (code "92") (name "Net-(E25D-I0)") (class "Default")
      (node (ref "E25") (pin "11") (pinfunction "I0_11") (pintype "input"))
      (node (ref "E30") (pin "8") (pinfunction "O_8") (pintype "output"))
    )
    (net (code "93") (name "Net-(E25D-I1)") (class "Default")
      (node (ref "E25") (pin "12") (pinfunction "I1_12") (pintype "input"))
      (node (ref "E26") (pin "1") (pinfunction "O_1") (pintype "output"))
    )
    (net (code "94") (name "Net-(E26B-O)") (class "Default")
      (node (ref "E26") (pin "4") (pinfunction "O_4") (pintype "output"))
      (node (ref "E33") (pin "8") (pinfunction "I0_8") (pintype "input"))
      (node (ref "E33") (pin "9") (pinfunction "I1_9") (pintype "input"))
    )
    (net (code "95") (name "Net-(E29C-I1)") (class "Default")
      (node (ref "E29") (pin "10") (pinfunction "I1_10") (pintype "input"))
      (node (ref "E29") (pin "11") (pinfunction "O_11") (pintype "output"))
    )
    (net (code "96") (name "Net-(E34A-A)") (class "Default")
      (node (ref "E34") (pin "15") (pinfunction "A_15") (pintype "input"))
      (node (ref "E35") (pin "14") (pinfunction "O_14") (pintype "output"))
      (node (ref "E38") (pin "15") (pinfunction "A_15") (pintype "input"))
    )
    (net (code "97") (name "Net-(E34A-B)") (class "Default")
      (node (ref "E34") (pin "14") (pinfunction "B_14") (pintype "input"))
      (node (ref "E35") (pin "13") (pinfunction "O_13") (pintype "output"))
      (node (ref "E38") (pin "14") (pinfunction "B_14") (pintype "input"))
    )
    (net (code "98") (name "Net-(E34A-C)") (class "Default")
      (node (ref "E34") (pin "1") (pinfunction "C_1") (pintype "input"))
      (node (ref "E35") (pin "3") (pinfunction "O_3") (pintype "output"))
      (node (ref "E38") (pin "1") (pinfunction "C_1") (pintype "input"))
    )
    (net (code "99") (name "Net-(E36D-I0)") (class "Default")
      (node (ref "E36") (pin "1") (pinfunction "I0_1") (pintype "input"))
      (node (ref "E45") (pin "6") (pinfunction "~{Q}_6") (pintype "output"))
    )
    (net (code "100") (name "Net-(E36D-I1)") (class "Default")
      (node (ref "E36") (pin "2") (pinfunction "I1_2") (pintype "input"))
      (node (ref "E49") (pin "6") (pinfunction "~{Q}_6") (pintype "output"))
    )
    (net (code "101") (name "Net-(E36D-I2)") (class "Default")
      (node (ref "E36") (pin "3") (pinfunction "I2_3") (pintype "input"))
      (node (ref "E44") (pin "8") (pinfunction "~{Q}_8") (pintype "output"))
    )
    (net (code "102") (name "Net-(E36D-I3)") (class "Default")
      (node (ref "E36") (pin "4") (pinfunction "I3_4") (pintype "input"))
      (node (ref "E44") (pin "6") (pinfunction "~{Q}_6") (pintype "output"))
    )
    (net (code "103") (name "Net-(E36D-I4)") (class "Default")
      (node (ref "E36") (pin "5") (pinfunction "I4_5") (pintype "input"))
      (node (ref "E48") (pin "8") (pinfunction "~{Q}_8") (pintype "output"))
    )
    (net (code "104") (name "Net-(E36D-I5)") (class "Default")
      (node (ref "E36") (pin "6") (pinfunction "I5_6") (pintype "input"))
      (node (ref "E48") (pin "6") (pinfunction "~{Q}_6") (pintype "output"))
    )
    (net (code "105") (name "Net-(E36D-I7)") (class "Default")
      (node (ref "E36") (pin "12") (pinfunction "I7_12") (pintype "input"))
      (node (ref "E45") (pin "8") (pinfunction "~{Q}_8") (pintype "output"))
    )
    (net (code "106") (name "Net-(E37C-I0)") (class "Default")
      (node (ref "E37") (pin "1") (pinfunction "I0_1") (pintype "input"))
      (node (ref "E37") (pin "2") (pinfunction "I1_2") (pintype "input"))
      (node (ref "E37") (pin "4") (pinfunction "I2_4") (pintype "input"))
      (node (ref "E37") (pin "5") (pinfunction "I3_5") (pintype "input"))
      (node (ref "E6") (pin "6") (pinfunction "O_6") (pintype "output"))
    )
    (net (code "107") (name "Net-(E39A-I0)") (class "Default")
      (node (ref "E39") (pin "2") (pinfunction "I0_2") (pintype "input"))
      (node (ref "E40") (pin "5") (pinfunction "Q_5") (pintype "output"))
      (node (ref "E51") (pin "12") (pinfunction "D_12") (pintype "input"))
    )
    (net (code "108") (name "Net-(E39B-I0)") (class "Default")
      (node (ref "E39") (pin "5") (pinfunction "I0_5") (pintype "input"))
      (node (ref "E40") (pin "2") (pinfunction "D_2") (pintype "input"))
      (node (ref "E41") (pin "5") (pinfunction "Q_5") (pintype "output"))
    )
    (net (code "109") (name "Net-(E39C-I1)") (class "Default")
      (node (ref "E39") (pin "9") (pinfunction "I1_9") (pintype "input"))
      (node (ref "E41") (pin "2") (pinfunction "D_2") (pintype "input"))
      (node (ref "E41") (pin "9") (pinfunction "Q_9") (pintype "output"))
    )
    (net (code "110") (name "Net-(E39D-I1)") (class "Default")
      (node (ref "E39") (pin "12") (pinfunction "I1_12") (pintype "input"))
      (node (ref "E40") (pin "9") (pinfunction "Q_9") (pintype "output"))
      (node (ref "E41") (pin "12") (pinfunction "D_12") (pintype "input"))
    )
    (net (code "111") (name "Net-(E43A-O)") (class "Default")
      (node (ref "E43") (pin "3") (pinfunction "O_3") (pintype "output"))
      (node (ref "E45") (pin "4") (pinfunction "PRE_4") (pintype "input"))
    )
    (net (code "112") (name "Net-(E43B-O)") (class "Default")
      (node (ref "E43") (pin "2") (pinfunction "O_2") (pintype "output"))
      (node (ref "E44") (pin "4") (pinfunction "PRE_4") (pintype "input"))
    )
    (net (code "113") (name "Net-(E43C-O)") (class "Default")
      (node (ref "E43") (pin "14") (pinfunction "O_14") (pintype "output"))
      (node (ref "E44") (pin "10") (pinfunction "PRE_10") (pintype "input"))
    )
    (net (code "114") (name "Net-(E43D-O)") (class "Default")
      (node (ref "E43") (pin "13") (pinfunction "O_13") (pintype "output"))
      (node (ref "E45") (pin "10") (pinfunction "PRE_10") (pintype "input"))
    )
    (net (code "115") (name "Net-(E44A-D)") (class "Default")
      (node (ref "E44") (pin "2") (pinfunction "D_2") (pintype "input"))
      (node (ref "E45") (pin "5") (pinfunction "Q_5") (pintype "output"))
    )
    (net (code "116") (name "Net-(E44A-Q)") (class "Default")
      (node (ref "E44") (pin "12") (pinfunction "D_12") (pintype "input"))
      (node (ref "E44") (pin "5") (pinfunction "Q_5") (pintype "output"))
    )
    (net (code "117") (name "Net-(E44B-Q)") (class "Default")
      (node (ref "E44") (pin "9") (pinfunction "Q_9") (pintype "output"))
      (node (ref "E45") (pin "12") (pinfunction "D_12") (pintype "input"))
    )
    (net (code "118") (name "Net-(E45B-Q)") (class "Default")
      (node (ref "E45") (pin "9") (pinfunction "Q_9") (pintype "output"))
      (node (ref "E49") (pin "2") (pinfunction "D_2") (pintype "input"))
    )
    (net (code "119") (name "Net-(E46A-D)") (class "Default")
      (node (ref "E46") (pin "2") (pinfunction "D_2") (pintype "input"))
      (node (ref "E49") (pin "9") (pinfunction "Q_9") (pintype "output"))
    )
    (net (code "120") (name "Net-(E46A-Q)") (class "Default")
      (node (ref "E46") (pin "5") (pinfunction "Q_5") (pintype "output"))
      (node (ref "R21") (pin "1") (pinfunction "1_1") (pintype "passive"))
      (node (ref "R22") (pin "1") (pinfunction "1_1") (pintype "passive"))
      (node (ref "U$1") (pin "DB1") (pinfunction "1_DB1") (pintype "bidirectional"))
    )
    (net (code "121") (name "Net-(E46B-Q)") (class "Default")
      (node (ref "E46") (pin "9") (pinfunction "Q_9") (pintype "output"))
      (node (ref "U$1") (pin "DA1") (pinfunction "1_DA1") (pintype "bidirectional"))
    )
    (net (code "122") (name "Net-(E46B-~{Q})") (class "Default")
      (node (ref "E46") (pin "8") (pinfunction "~{Q}_8") (pintype "output"))
      (node (ref "Q2") (pin "2") (pinfunction "B_2") (pintype "passive"))
      (node (ref "R13") (pin "1") (pinfunction "1_1") (pintype "passive"))
    )
    (net (code "123") (name "Net-(E47A-O)") (class "Default")
      (node (ref "E47") (pin "3") (pinfunction "O_3") (pintype "output"))
      (node (ref "E49") (pin "4") (pinfunction "PRE_4") (pintype "input"))
    )
    (net (code "124") (name "Net-(E47B-O)") (class "Default")
      (node (ref "E47") (pin "2") (pinfunction "O_2") (pintype "output"))
      (node (ref "E48") (pin "4") (pinfunction "PRE_4") (pintype "input"))
    )
    (net (code "125") (name "Net-(E47C-O)") (class "Default")
      (node (ref "E47") (pin "14") (pinfunction "O_14") (pintype "output"))
      (node (ref "E48") (pin "10") (pinfunction "PRE_10") (pintype "input"))
    )
    (net (code "126") (name "Net-(E47D-O)") (class "Default")
      (node (ref "E47") (pin "13") (pinfunction "O_13") (pintype "output"))
      (node (ref "E49") (pin "10") (pinfunction "PRE_10") (pintype "input"))
    )
    (net (code "127") (name "Net-(E48A-D)") (class "Default")
      (node (ref "E48") (pin "2") (pinfunction "D_2") (pintype "input"))
      (node (ref "E49") (pin "5") (pinfunction "Q_5") (pintype "output"))
    )
    (net (code "128") (name "Net-(E48A-Q)") (class "Default")
      (node (ref "E48") (pin "12") (pinfunction "D_12") (pintype "input"))
      (node (ref "E48") (pin "5") (pinfunction "Q_5") (pintype "output"))
    )
    (net (code "129") (name "Net-(E48B-Q)") (class "Default")
      (node (ref "E48") (pin "9") (pinfunction "Q_9") (pintype "output"))
      (node (ref "E49") (pin "12") (pinfunction "D_12") (pintype "input"))
    )
    (net (code "130") (name "Net-(E50A-I0)") (class "Default")
      (node (ref "E50") (pin "2") (pinfunction "I0_2") (pintype "input"))
      (node (ref "E51") (pin "5") (pinfunction "Q_5") (pintype "output"))
    )
    (net (code "131") (name "Net-(E50B-I0)") (class "Default")
      (node (ref "E50") (pin "5") (pinfunction "I0_5") (pintype "input"))
      (node (ref "E51") (pin "2") (pinfunction "D_2") (pintype "input"))
      (node (ref "E52") (pin "5") (pinfunction "Q_5") (pintype "output"))
    )
    (net (code "132") (name "Net-(E50C-I1)") (class "Default")
      (node (ref "E50") (pin "9") (pinfunction "I1_9") (pintype "input"))
      (node (ref "E52") (pin "2") (pinfunction "D_2") (pintype "input"))
      (node (ref "E52") (pin "9") (pinfunction "Q_9") (pintype "output"))
    )
    (net (code "133") (name "Net-(E50D-I1)") (class "Default")
      (node (ref "E50") (pin "12") (pinfunction "I1_12") (pintype "input"))
      (node (ref "E51") (pin "9") (pinfunction "Q_9") (pintype "output"))
      (node (ref "E52") (pin "12") (pinfunction "D_12") (pintype "input"))
    )
    (net (code "134") (name "Net-(Q1-B)") (class "Default")
      (node (ref "C3") (pin "1") (pinfunction "1_1") (pintype "passive"))
      (node (ref "C4") (pin "1") (pinfunction "1_1") (pintype "passive"))
      (node (ref "Q1") (pin "2") (pinfunction "B_2") (pintype "passive"))
      (node (ref "R3") (pin "1") (pinfunction "1_1") (pintype "passive"))
      (node (ref "V3") (pin "1") (pinfunction "1_1") (pintype "passive"))
      (node (ref "V3") (pin "2") (pinfunction "2_2") (pintype "passive"))
    )
    (net (code "135") (name "Net-(Q1-E)") (class "Default")
      (node (ref "C4") (pin "2") (pinfunction "2_2") (pintype "passive"))
      (node (ref "C5") (pin "1") (pinfunction "1_1") (pintype "passive"))
      (node (ref "C6") (pin "1") (pinfunction "1_1") (pintype "passive"))
      (node (ref "Q1") (pin "1") (pinfunction "E_1") (pintype "passive"))
      (node (ref "R4") (pin "2") (pinfunction "2_2") (pintype "passive"))
      (node (ref "V4") (pin "1") (pinfunction "1_1") (pintype "passive"))
      (node (ref "V4") (pin "2") (pinfunction "2_2") (pintype "passive"))
    )
    (net (code "136") (name "Net-(Q2-E)") (class "Default")
      (node (ref "D4") (pin "C") (pinfunction "C_C") (pintype "passive"))
      (node (ref "Q2") (pin "1") (pinfunction "E_1") (pintype "passive"))
      (node (ref "R14") (pin "1") (pinfunction "1_1") (pintype "passive"))
    )
    (net (code "137") (name "Net-(Q3-B)") (class "Default")
      (node (ref "C13") (pin "1") (pinfunction "1_1") (pintype "passive"))
      (node (ref "Q3") (pin "2") (pinfunction "B_2") (pintype "passive"))
      (node (ref "R22") (pin "2") (pinfunction "2_2") (pintype "passive"))
    )
    (net (code "138") (name "Net-(R29-Pad2)") (class "Default")
      (node (ref "R29") (pin "2") (pinfunction "2_2") (pintype "passive"))
      (node (ref "R7") (pin "1") (pinfunction "1_1") (pintype "passive"))
      (node (ref "T1") (pin "16") (pinfunction "16_16") (pintype "passive"))
    )
    (net (code "139") (name "Net-(T1-Pad2)") (class "Default")
      (node (ref "T1") (pin "2") (pinfunction "2_2") (pintype "passive"))
      (node (ref "T1") (pin "3") (pinfunction "3_3") (pintype "passive"))
    )
    (net (code "140") (name "Net-(T1-Pad6)") (class "Default")
      (node (ref "T1") (pin "6") (pinfunction "6_6") (pintype "passive"))
      (node (ref "T1") (pin "7") (pinfunction "7_7") (pintype "passive"))
    )
    (net (code "141") (name "Net-(T1-Pad10)") (class "Default")
      (node (ref "T1") (pin "10") (pinfunction "10_10") (pintype "passive"))
      (node (ref "T1") (pin "11") (pinfunction "11_11") (pintype "passive"))
    )
    (net (code "142") (name "Net-(T1-Pad12)") (class "Default")
      (node (ref "T1") (pin "12") (pinfunction "12_12") (pintype "passive"))
      (node (ref "T1") (pin "13") (pinfunction "13_13") (pintype "passive"))
    )
    (net (code "143") (name "Net-(T1-Pad14)") (class "Default")
      (node (ref "T1") (pin "14") (pinfunction "14_14") (pintype "passive"))
      (node (ref "T1") (pin "15") (pinfunction "15_15") (pintype "passive"))
    )
    (net (code "144") (name "POWER_OK") (class "Default")
      (node (ref "E10") (pin "5") (pinfunction "I1_5") (pintype "input"))
      (node (ref "U$1") (pin "BV2") (pinfunction "1_BV2") (pintype "bidirectional"))
    )
    (net (code "145") (name "PRESET") (class "Default")
      (node (ref "E2") (pin "2") (pinfunction "I1_2") (pintype "input"))
      (node (ref "E6") (pin "2") (pinfunction "O_2") (pintype "output"))
    )
    (net (code "146") (name "RCVR_CLK") (class "Default")
      (node (ref "E12") (pin "3") (pinfunction "CLK_3") (pintype "input"))
      (node (ref "E13") (pin "9") (pinfunction "QB_9") (pintype "output"))
      (node (ref "E2") (pin "1") (pinfunction "I0_1") (pintype "input"))
    )
    (net (code "147") (name "READ_BUFFER") (class "Default")
      (node (ref "E30") (pin "6") (pinfunction "O_6") (pintype "output"))
      (node (ref "E31") (pin "5") (pinfunction "I0_5") (pintype "input"))
      (node (ref "E31") (pin "6") (pinfunction "I1_6") (pintype "input"))
      (node (ref "E39") (pin "11") (pinfunction "I0_11") (pintype "input"))
      (node (ref "E39") (pin "3") (pinfunction "I1_3") (pintype "input"))
      (node (ref "E39") (pin "6") (pinfunction "I1_6") (pintype "input"))
      (node (ref "E39") (pin "8") (pinfunction "I0_8") (pintype "input"))
      (node (ref "E50") (pin "11") (pinfunction "I0_11") (pintype "input"))
      (node (ref "E50") (pin "3") (pinfunction "I1_3") (pintype "input"))
      (node (ref "E50") (pin "6") (pinfunction "I1_6") (pintype "input"))
      (node (ref "E50") (pin "8") (pinfunction "I0_8") (pintype "input"))
    )
    (net (code "148") (name "RR_CLK") (class "Default")
      (node (ref "E40") (pin "8") (pinfunction "~{Q}_8") (pintype "output"))
      (node (ref "E46") (pin "11") (pinfunction "CLK_11") (pintype "input"))
    )
    (net (code "149") (name "RR_CTL") (class "Default")
      (node (ref "6") (pin "1") (pinfunction "P_1") (pintype "passive"))
      (node (ref "C9") (pin "1") (pinfunction "1_1") (pintype "passive"))
      (node (ref "D7") (pin "C") (pinfunction "C_C") (pintype "passive"))
      (node (ref "Q2") (pin "3") (pinfunction "C_3") (pintype "passive"))
    )
    (net (code "150") (name "RX_ACTIVE") (class "Default")
      (node (ref "C10") (pin "2") (pinfunction "2_2") (pintype "passive"))
      (node (ref "E1") (pin "13") (pinfunction "CLR_13") (pintype "input"))
      (node (ref "E1") (pin "5") (pinfunction "Q_5") (pintype "output"))
      (node (ref "E3") (pin "4") (pinfunction "I0_4") (pintype "input"))
      (node (ref "R15") (pin "1") (pinfunction "1_1") (pintype "passive"))
      (node (ref "U$1") (pin "AB1") (pinfunction "1_AB1") (pintype "bidirectional"))
    )
    (net (code "151") (name "RX_CLK") (class "Default")
      (node (ref "E12") (pin "11") (pinfunction "CLK_11") (pintype "input"))
      (node (ref "E2") (pin "10") (pinfunction "I1_10") (pintype "input"))
      (node (ref "E37") (pin "6") (pinfunction "O_6") (pintype "output"))
      (node (ref "E40") (pin "11") (pinfunction "CLK_11") (pintype "input"))
      (node (ref "E40") (pin "3") (pinfunction "CLK_3") (pintype "input"))
      (node (ref "E41") (pin "11") (pinfunction "CLK_11") (pintype "input"))
      (node (ref "E41") (pin "3") (pinfunction "CLK_3") (pintype "input"))
      (node (ref "E42") (pin "11") (pinfunction "CLK_11") (pintype "input"))
      (node (ref "E51") (pin "11") (pinfunction "CLK_11") (pintype "input"))
      (node (ref "E51") (pin "3") (pinfunction "CLK_3") (pintype "input"))
      (node (ref "E52") (pin "11") (pinfunction "CLK_11") (pintype "input"))
      (node (ref "E52") (pin "3") (pinfunction "CLK_3") (pintype "input"))
    )
    (net (code "152") (name "RX_DATA") (class "Default")
      (node (ref "E2") (pin "11") (pinfunction "I2_11") (pintype "input"))
      (node (ref "E3") (pin "8") (pinfunction "O_8") (pintype "output"))
      (node (ref "E40") (pin "12") (pinfunction "D_12") (pintype "input"))
    )
    (net (code "153") (name "SW") (class "Default")
      (node (ref "E27") (pin "6") (pinfunction "I0_6") (pintype "input"))
      (node (ref "U$1") (pin "DV2") (pinfunction "1_DV2") (pintype "bidirectional"))
    )
    (net (code "154") (name "TP3") (class "Default")
      (node (ref "E27") (pin "4") (pinfunction "I0_4") (pintype "input"))
      (node (ref "U$1") (pin "CH2") (pinfunction "1_CH2") (pintype "bidirectional"))
    )
    (net (code "155") (name "VCC") (class "Default")
      (node (ref "C1") (pin "+") (pinfunction "+_+") (pintype "passive"))
      (node (ref "C17") (pin "+") (pinfunction "+_+") (pintype "passive"))
      (node (ref "C18") (pin "+") (pinfunction "+_+") (pintype "passive"))
      (node (ref "C19") (pin "+") (pinfunction "+_+") (pintype "passive"))
      (node (ref "C2") (pin "1") (pinfunction "1_1") (pintype "passive"))
      (node (ref "C20") (pin "1") (pinfunction "1_1") (pintype "passive"))
      (node (ref "C21") (pin "1") (pinfunction "1_1") (pintype "passive"))
      (node (ref "C22") (pin "1") (pinfunction "1_1") (pintype "passive"))
      (node (ref "C23") (pin "1") (pinfunction "1_1") (pintype "passive"))
      (node (ref "C24") (pin "1") (pinfunction "1_1") (pintype "passive"))
      (node (ref "C25") (pin "1") (pinfunction "1_1") (pintype "passive"))
      (node (ref "C26") (pin "1") (pinfunction "1_1") (pintype "passive"))
      (node (ref "C27") (pin "1") (pinfunction "1_1") (pintype "passive"))
      (node (ref "C28") (pin "1") (pinfunction "1_1") (pintype "passive"))
      (node (ref "C29") (pin "1") (pinfunction "1_1") (pintype "passive"))
      (node (ref "C30") (pin "1") (pinfunction "1_1") (pintype "passive"))
      (node (ref "C31") (pin "1") (pinfunction "1_1") (pintype "passive"))
      (node (ref "C32") (pin "1") (pinfunction "1_1") (pintype "passive"))
      (node (ref "C33") (pin "1") (pinfunction "1_1") (pintype "passive"))
      (node (ref "C34") (pin "1") (pinfunction "1_1") (pintype "passive"))
      (node (ref "C35") (pin "1") (pinfunction "1_1") (pintype "passive"))
      (node (ref "C36") (pin "1") (pinfunction "1_1") (pintype "passive"))
      (node (ref "C37") (pin "1") (pinfunction "1_1") (pintype "passive"))
      (node (ref "C38") (pin "1") (pinfunction "1_1") (pintype "passive"))
      (node (ref "C39") (pin "1") (pinfunction "1_1") (pintype "passive"))
      (node (ref "C40") (pin "1") (pinfunction "1_1") (pintype "passive"))
      (node (ref "C41") (pin "1") (pinfunction "1_1") (pintype "passive"))
      (node (ref "C42") (pin "1") (pinfunction "1_1") (pintype "passive"))
      (node (ref "C43") (pin "1") (pinfunction "1_1") (pintype "passive"))
      (node (ref "C44") (pin "1") (pinfunction "1_1") (pintype "passive"))
      (node (ref "C45") (pin "1") (pinfunction "1_1") (pintype "passive"))
      (node (ref "C46") (pin "1") (pinfunction "1_1") (pintype "passive"))
      (node (ref "C47") (pin "1") (pinfunction "1_1") (pintype "passive"))
      (node (ref "C48") (pin "1") (pinfunction "1_1") (pintype "passive"))
      (node (ref "C49") (pin "1") (pinfunction "1_1") (pintype "passive"))
      (node (ref "C50") (pin "1") (pinfunction "1_1") (pintype "passive"))
      (node (ref "C51") (pin "1") (pinfunction "1_1") (pintype "passive"))
      (node (ref "C52") (pin "1") (pinfunction "1_1") (pintype "passive"))
      (node (ref "C53") (pin "1") (pinfunction "1_1") (pintype "passive"))
      (node (ref "C54") (pin "1") (pinfunction "1_1") (pintype "passive"))
      (node (ref "C55") (pin "1") (pinfunction "1_1") (pintype "passive"))
      (node (ref "C56") (pin "1") (pinfunction "1_1") (pintype "passive"))
      (node (ref "C57") (pin "1") (pinfunction "1_1") (pintype "passive"))
      (node (ref "C58") (pin "1") (pinfunction "1_1") (pintype "passive"))
      (node (ref "C59") (pin "1") (pinfunction "1_1") (pintype "passive"))
      (node (ref "C60") (pin "1") (pinfunction "1_1") (pintype "passive"))
      (node (ref "C61") (pin "1") (pinfunction "1_1") (pintype "passive"))
      (node (ref "C62") (pin "1") (pinfunction "1_1") (pintype "passive"))
      (node (ref "C63") (pin "1") (pinfunction "1_1") (pintype "passive"))
      (node (ref "C64") (pin "1") (pinfunction "1_1") (pintype "passive"))
      (node (ref "C65") (pin "1") (pinfunction "1_1") (pintype "passive"))
      (node (ref "C66") (pin "1") (pinfunction "1_1") (pintype "passive"))
      (node (ref "C67") (pin "1") (pinfunction "1_1") (pintype "passive"))
      (node (ref "C68") (pin "1") (pinfunction "1_1") (pintype "passive"))
      (node (ref "C69") (pin "1") (pinfunction "1_1") (pintype "passive"))
      (node (ref "C70") (pin "1") (pinfunction "1_1") (pintype "passive"))
      (node (ref "C71") (pin "1") (pinfunction "1_1") (pintype "passive"))
      (node (ref "D2") (pin "C") (pinfunction "C_C") (pintype "passive"))
      (node (ref "D9") (pin "C") (pinfunction "C_C") (pintype "passive"))
      (node (ref "Q1") (pin "3") (pinfunction "C_3") (pintype "passive"))
      (node (ref "R1") (pin "2") (pinfunction "2_2") (pintype "passive"))
      (node (ref "R11") (pin "2") (pinfunction "2_2") (pintype "passive"))
      (node (ref "R13") (pin "2") (pinfunction "2_2") (pintype "passive"))
      (node (ref "R14") (pin "2") (pinfunction "2_2") (pintype "passive"))
      (node (ref "R15") (pin "2") (pinfunction "2_2") (pintype "passive"))
      (node (ref "R17") (pin "2") (pinfunction "2_2") (pintype "passive"))
      (node (ref "R18") (pin "2") (pinfunction "2_2") (pintype "passive"))
      (node (ref "R20") (pin "2") (pinfunction "2_2") (pintype "passive"))
      (node (ref "R21") (pin "2") (pinfunction "2_2") (pintype "passive"))
      (node (ref "R26") (pin "2") (pinfunction "2_2") (pintype "passive"))
      (node (ref "R28") (pin "2") (pinfunction "2_2") (pintype "passive"))
      (node (ref "R3") (pin "2") (pinfunction "2_2") (pintype "passive"))
      (node (ref "R5") (pin "2") (pinfunction "2_2") (pintype "passive"))
      (node (ref "R6") (pin "2") (pinfunction "2_2") (pintype "passive"))
      (node (ref "R8") (pin "2") (pinfunction "2_2") (pintype "passive"))
      (node (ref "R9") (pin "2") (pinfunction "2_2") (pintype "passive"))
      (node (ref "U$1") (pin "AA2") (pinfunction "1_AA2") (pintype "bidirectional"))
      (node (ref "U$1") (pin "BA2") (pinfunction "1_BA2") (pintype "bidirectional"))
      (node (ref "U$1") (pin "CA2") (pinfunction "1_CA2") (pintype "bidirectional"))
    )
    (net (code "156") (name "XMIT_ACTIVE") (class "Default")
      (node (ref "E15") (pin "2") (pinfunction "D_2") (pintype "input"))
      (node (ref "E15") (pin "9") (pinfunction "Q_9") (pintype "output"))
      (node (ref "E16") (pin "13") (pinfunction "I1_13") (pintype "input"))
      (node (ref "E17") (pin "10") (pinfunction "I1_10") (pintype "input"))
      (node (ref "E46") (pin "4") (pinfunction "PRE_4") (pintype "input"))
      (node (ref "U$1") (pin "BA1") (pinfunction "1_BA1") (pintype "bidirectional"))
    )
    (net (code "157") (name "XMIT_CLK") (class "Default")
      (node (ref "E13") (pin "11") (pinfunction "QD_11") (pintype "output"))
      (node (ref "E15") (pin "11") (pinfunction "CLK_11") (pintype "input"))
      (node (ref "E15") (pin "3") (pinfunction "CLK_3") (pintype "input"))
      (node (ref "E19") (pin "11") (pinfunction "CLK_11") (pintype "input"))
      (node (ref "E19") (pin "3") (pinfunction "CLK_3") (pintype "input"))
      (node (ref "E20") (pin "3") (pinfunction "CLK_3") (pintype "input"))
    )
    (net (code "158") (name "unconnected-(E1B-~{Q}-Pad8)") (class "Default")
      (node (ref "E1") (pin "8") (pinfunction "~{Q}_8") (pintype "output"))
    )
    (net (code "159") (name "unconnected-(E4A-QB-Pad9)") (class "Default")
      (node (ref "E4") (pin "9") (pinfunction "QB_9") (pintype "output"))
    )
    (net (code "160") (name "unconnected-(E4A-QC-Pad8)") (class "Default")
      (node (ref "E4") (pin "8") (pinfunction "QC_8") (pintype "output"))
    )
    (net (code "161") (name "unconnected-(E5A-CKA-Pad14)") (class "Default")
      (node (ref "E5") (pin "14") (pinfunction "CKA_14") (pintype "input"))
    )
    (net (code "162") (name "unconnected-(E5A-QA-Pad12)") (class "Default")
      (node (ref "E5") (pin "12") (pinfunction "QA_12") (pintype "output"))
    )
    (net (code "163") (name "unconnected-(E5A-QB-Pad9)") (class "Default")
      (node (ref "E5") (pin "9") (pinfunction "QB_9") (pintype "output"))
    )
    (net (code "164") (name "unconnected-(E5A-QC-Pad8)") (class "Default")
      (node (ref "E5") (pin "8") (pinfunction "QC_8") (pintype "output"))
    )
    (net (code "165") (name "unconnected-(E7B-Q-Pad9)") (class "Default")
      (node (ref "E7") (pin "9") (pinfunction "Q_9") (pintype "output"))
    )
    (net (code "166") (name "unconnected-(E8A-QB-Pad9)") (class "Default")
      (node (ref "E8") (pin "9") (pinfunction "QB_9") (pintype "output"))
    )
    (net (code "167") (name "unconnected-(E8A-QC-Pad8)") (class "Default")
      (node (ref "E8") (pin "8") (pinfunction "QC_8") (pintype "output"))
    )
    (net (code "168") (name "unconnected-(E9A-CLR-Pad2)") (class "Default")
      (node (ref "E9") (pin "2") (pinfunction "CLR_2") (pintype "input"))
    )
    (net (code "169") (name "unconnected-(E9A-PRE-Pad13)") (class "Default")
      (node (ref "E9") (pin "13") (pinfunction "PRE_13") (pintype "input"))
    )
    (net (code "170") (name "unconnected-(E13A-QC-Pad8)") (class "Default")
      (node (ref "E13") (pin "8") (pinfunction "QC_8") (pintype "output"))
    )
    (net (code "171") (name "unconnected-(E19A-Q-Pad5)") (class "Default")
      (node (ref "E19") (pin "5") (pinfunction "Q_5") (pintype "output"))
    )
    (net (code "172") (name "unconnected-(E19B-~{Q}-Pad8)") (class "Default")
      (node (ref "E19") (pin "8") (pinfunction "~{Q}_8") (pintype "output"))
    )
    (net (code "173") (name "unconnected-(E21B-Q-Pad9)") (class "Default")
      (node (ref "E21") (pin "9") (pinfunction "Q_9") (pintype "output"))
    )
    (net (code "174") (name "unconnected-(E34A-3-Pad10)") (class "Default")
      (node (ref "E34") (pin "10") (pinfunction "3_10") (pintype "output"))
    )
    (net (code "175") (name "unconnected-(E34A-7-Pad5)") (class "Default")
      (node (ref "E34") (pin "5") (pinfunction "7_5") (pintype "output"))
    )
    (net (code "176") (name "unconnected-(E34A-8-Pad6)") (class "Default")
      (node (ref "E34") (pin "6") (pinfunction "8_6") (pintype "output"))
    )
    (net (code "177") (name "unconnected-(E34A-9-Pad7)") (class "Default")
      (node (ref "E34") (pin "7") (pinfunction "9_7") (pintype "output"))
    )
    (net (code "178") (name "unconnected-(E38A-3-Pad10)") (class "Default")
      (node (ref "E38") (pin "10") (pinfunction "3_10") (pintype "output"))
    )
    (net (code "179") (name "unconnected-(E38A-7-Pad5)") (class "Default")
      (node (ref "E38") (pin "5") (pinfunction "7_5") (pintype "output"))
    )
    (net (code "180") (name "unconnected-(E38A-8-Pad6)") (class "Default")
      (node (ref "E38") (pin "6") (pinfunction "8_6") (pintype "output"))
    )
    (net (code "181") (name "unconnected-(E38A-9-Pad7)") (class "Default")
      (node (ref "E38") (pin "7") (pinfunction "9_7") (pintype "output"))
    )
    (net (code "182") (name "unconnected-(E40A-~{Q}-Pad6)") (class "Default")
      (node (ref "E40") (pin "6") (pinfunction "~{Q}_6") (pintype "output"))
    )
    (net (code "183") (name "unconnected-(E41A-~{Q}-Pad6)") (class "Default")
      (node (ref "E41") (pin "6") (pinfunction "~{Q}_6") (pintype "output"))
    )
    (net (code "184") (name "unconnected-(E41B-~{Q}-Pad8)") (class "Default")
      (node (ref "E41") (pin "8") (pinfunction "~{Q}_8") (pintype "output"))
    )
    (net (code "185") (name "unconnected-(E42B-Q-Pad9)") (class "Default")
      (node (ref "E42") (pin "9") (pinfunction "Q_9") (pintype "output"))
    )
    (net (code "186") (name "unconnected-(E46A-~{Q}-Pad6)") (class "Default")
      (node (ref "E46") (pin "6") (pinfunction "~{Q}_6") (pintype "output"))
    )
    (net (code "187") (name "unconnected-(E49B-~{Q}-Pad8)") (class "Default")
      (node (ref "E49") (pin "8") (pinfunction "~{Q}_8") (pintype "output"))
    )
    (net (code "188") (name "unconnected-(E51B-~{Q}-Pad8)") (class "Default")
      (node (ref "E51") (pin "8") (pinfunction "~{Q}_8") (pintype "output"))
    )
    (net (code "189") (name "unconnected-(E52A-~{Q}-Pad6)") (class "Default")
      (node (ref "E52") (pin "6") (pinfunction "~{Q}_6") (pintype "output"))
    )
    (net (code "190") (name "unconnected-(E52B-~{Q}-Pad8)") (class "Default")
      (node (ref "E52") (pin "8") (pinfunction "~{Q}_8") (pintype "output"))
    )
    (net (code "191") (name "~{603}") (class "Default")
      (node (ref "E22") (pin "8") (pinfunction "O_8") (pintype "output"))
      (node (ref "E34") (pin "2") (pinfunction "D_2") (pintype "input"))
    )
    (net (code "192") (name "~{604}") (class "Default")
      (node (ref "E32") (pin "10") (pinfunction "O_10") (pintype "open_collector"))
      (node (ref "E38") (pin "2") (pinfunction "D_2") (pintype "input"))
      (node (ref "R9") (pin "1") (pinfunction "1_1") (pintype "passive"))
    )
    (net (code "193") (name "~{C0}") (class "Default")
      (node (ref "E31") (pin "10") (pinfunction "O_10") (pintype "open_collector"))
      (node (ref "U$1") (pin "CE1") (pinfunction "1_CE1") (pintype "bidirectional"))
    )
    (net (code "194") (name "~{C1}") (class "Default")
      (node (ref "E31") (pin "1") (pinfunction "O_1") (pintype "open_collector"))
      (node (ref "E31") (pin "4") (pinfunction "O_4") (pintype "open_collector"))
      (node (ref "U$1") (pin "CH1") (pinfunction "1_CH1") (pintype "bidirectional"))
    )
    (net (code "195") (name "~{CLR_ACTIVE}") (class "Default")
      (node (ref "E1") (pin "1") (pinfunction "CLR_1") (pintype "input"))
      (node (ref "E25") (pin "10") (pinfunction "O_10") (pintype "output"))
    )
    (net (code "196") (name "~{DATA4}") (class "Default")
      (node (ref "E39") (pin "13") (pinfunction "O_13") (pintype "open_collector"))
      (node (ref "E43") (pin "4") (pinfunction "I0_4") (pintype "input"))
      (node (ref "U$1") (pin "BR1") (pinfunction "1_BR1") (pintype "bidirectional"))
    )
    (net (code "197") (name "~{DATA5}") (class "Default")
      (node (ref "E39") (pin "10") (pinfunction "O_10") (pintype "open_collector"))
      (node (ref "E43") (pin "6") (pinfunction "I0_6") (pintype "input"))
      (node (ref "U$1") (pin "BS1") (pinfunction "1_BS1") (pintype "bidirectional"))
    )
    (net (code "198") (name "~{DATA6}") (class "Default")
      (node (ref "E39") (pin "4") (pinfunction "O_4") (pintype "open_collector"))
      (node (ref "E43") (pin "9") (pinfunction "I0_9") (pintype "input"))
      (node (ref "U$1") (pin "BU1") (pinfunction "1_BU1") (pintype "bidirectional"))
    )
    (net (code "199") (name "~{DATA7}") (class "Default")
      (node (ref "E39") (pin "1") (pinfunction "O_1") (pintype "open_collector"))
      (node (ref "E43") (pin "12") (pinfunction "I1_12") (pintype "input"))
      (node (ref "U$1") (pin "BV1") (pinfunction "1_BV1") (pintype "bidirectional"))
    )
    (net (code "200") (name "~{DATA8}") (class "Default")
      (node (ref "E47") (pin "4") (pinfunction "I0_4") (pintype "input"))
      (node (ref "E50") (pin "13") (pinfunction "O_13") (pintype "open_collector"))
      (node (ref "U$1") (pin "DR1") (pinfunction "1_DR1") (pintype "bidirectional"))
    )
    (net (code "201") (name "~{DATA9}") (class "Default")
      (node (ref "E47") (pin "6") (pinfunction "I0_6") (pintype "input"))
      (node (ref "E50") (pin "10") (pinfunction "O_10") (pintype "open_collector"))
      (node (ref "U$1") (pin "DS1") (pinfunction "1_DS1") (pintype "bidirectional"))
    )
    (net (code "202") (name "~{DATA10}") (class "Default")
      (node (ref "E47") (pin "9") (pinfunction "I0_9") (pintype "input"))
      (node (ref "E50") (pin "4") (pinfunction "O_4") (pintype "open_collector"))
      (node (ref "U$1") (pin "DU1") (pinfunction "1_DU1") (pintype "bidirectional"))
    )
    (net (code "203") (name "~{DATA11}") (class "Default")
      (node (ref "E27") (pin "12") (pinfunction "I1_12") (pintype "input"))
      (node (ref "E47") (pin "12") (pinfunction "I1_12") (pintype "input"))
      (node (ref "E50") (pin "1") (pinfunction "O_1") (pintype "open_collector"))
      (node (ref "U$1") (pin "DV1") (pinfunction "1_DV1") (pintype "bidirectional"))
    )
    (net (code "204") (name "~{DTX_ACTIVE}") (class "Default")
      (node (ref "E46") (pin "1") (pinfunction "CLR_1") (pintype "input"))
      (node (ref "E6") (pin "12") (pinfunction "O_12") (pintype "output"))
    )
    (net (code "205") (name "~{ENABLE}") (class "Default")
      (node (ref "E36") (pin "11") (pinfunction "I6_11") (pintype "input"))
      (node (ref "E42") (pin "6") (pinfunction "~{Q}_6") (pintype "output"))
    )
    (net (code "206") (name "~{FREQ_DIV}") (class "Default")
      (node (ref "E15") (pin "4") (pinfunction "PRE_4") (pintype "input"))
      (node (ref "E19") (pin "10") (pinfunction "PRE_10") (pintype "input"))
      (node (ref "E19") (pin "4") (pinfunction "PRE_4") (pintype "input"))
      (node (ref "E21") (pin "11") (pinfunction "CLK_11") (pintype "input"))
      (node (ref "E37") (pin "8") (pinfunction "O_8") (pintype "output"))
      (node (ref "E42") (pin "3") (pinfunction "CLK_3") (pintype "input"))
      (node (ref "E44") (pin "11") (pinfunction "CLK_11") (pintype "input"))
      (node (ref "E44") (pin "3") (pinfunction "CLK_3") (pintype "input"))
      (node (ref "E45") (pin "11") (pinfunction "CLK_11") (pintype "input"))
      (node (ref "E45") (pin "3") (pinfunction "CLK_3") (pintype "input"))
      (node (ref "E46") (pin "3") (pinfunction "CLK_3") (pintype "input"))
      (node (ref "E48") (pin "11") (pinfunction "CLK_11") (pintype "input"))
      (node (ref "E48") (pin "3") (pinfunction "CLK_3") (pintype "input"))
      (node (ref "E49") (pin "11") (pinfunction "CLK_11") (pintype "input"))
      (node (ref "E49") (pin "3") (pinfunction "CLK_3") (pintype "input"))
    )
    (net (code "207") (name "~{INITIALIZE}") (class "Default")
      (node (ref "E11") (pin "6") (pinfunction "O_6") (pintype "output"))
      (node (ref "E15") (pin "13") (pinfunction "CLR_13") (pintype "input"))
      (node (ref "E20") (pin "4") (pinfunction "PRE_4") (pintype "input"))
      (node (ref "E21") (pin "1") (pinfunction "CLR_1") (pintype "input"))
      (node (ref "E29") (pin "9") (pinfunction "I0_9") (pintype "input"))
      (node (ref "E30") (pin "9") (pinfunction "I0_9") (pintype "input"))
      (node (ref "E42") (pin "1") (pinfunction "CLR_1") (pintype "input"))
      (node (ref "E44") (pin "1") (pinfunction "CLR_1") (pintype "input"))
      (node (ref "E44") (pin "13") (pinfunction "CLR_13") (pintype "input"))
      (node (ref "E45") (pin "1") (pinfunction "CLR_1") (pintype "input"))
      (node (ref "E45") (pin "13") (pinfunction "CLR_13") (pintype "input"))
      (node (ref "E46") (pin "13") (pinfunction "CLR_13") (pintype "input"))
      (node (ref "E48") (pin "1") (pinfunction "CLR_1") (pintype "input"))
      (node (ref "E48") (pin "13") (pinfunction "CLR_13") (pintype "input"))
      (node (ref "E49") (pin "1") (pinfunction "CLR_1") (pintype "input"))
      (node (ref "E49") (pin "13") (pinfunction "CLR_13") (pintype "input"))
    )
    (net (code "208") (name "~{INTERNAL_IO}") (class "Default")
      (node (ref "E32") (pin "1") (pinfunction "O_1") (pintype "open_collector"))
      (node (ref "E32") (pin "4") (pinfunction "O_4") (pintype "open_collector"))
      (node (ref "U$1") (pin "CL1") (pinfunction "1_CL1") (pintype "bidirectional"))
    )
    (net (code "209") (name "~{INT_RQST}") (class "Default")
      (node (ref "E33") (pin "4") (pinfunction "O_4") (pintype "open_collector"))
      (node (ref "U$1") (pin "CP1") (pinfunction "1_CP1") (pintype "bidirectional"))
    )
    (net (code "210") (name "~{IO_PAUSE}") (class "Default")
      (node (ref "E27") (pin "7") (pinfunction "I1_7") (pintype "input"))
      (node (ref "U$1") (pin "CD1") (pinfunction "1_CD1") (pintype "bidirectional"))
    )
    (net (code "211") (name "~{KCC}") (class "Default")
      (node (ref "E30") (pin "2") (pinfunction "I1_2") (pintype "input"))
      (node (ref "E34") (pin "11") (pinfunction "2_11") (pintype "output"))
    )
    (net (code "212") (name "~{KCF}") (class "Default")
      (node (ref "E26") (pin "2") (pinfunction "I0_2") (pintype "input"))
      (node (ref "E34") (pin "13") (pinfunction "0_13") (pintype "output"))
    )
    (net (code "213") (name "~{KIE}") (class "Default")
      (node (ref "E26") (pin "12") (pinfunction "I1_12") (pintype "input"))
      (node (ref "E34") (pin "3") (pinfunction "5_3") (pintype "output"))
    )
    (net (code "214") (name "~{KRB}") (class "Default")
      (node (ref "E30") (pin "1") (pinfunction "I0_1") (pintype "input"))
      (node (ref "E30") (pin "5") (pinfunction "I1_5") (pintype "input"))
      (node (ref "E34") (pin "4") (pinfunction "6_4") (pintype "output"))
    )
    (net (code "215") (name "~{KRS}") (class "Default")
      (node (ref "E30") (pin "4") (pinfunction "I0_4") (pintype "input"))
      (node (ref "E34") (pin "9") (pinfunction "4_9") (pintype "output"))
    )
    (net (code "216") (name "~{KSF}") (class "Default")
      (node (ref "E26") (pin "6") (pinfunction "I1_6") (pintype "input"))
      (node (ref "E34") (pin "12") (pinfunction "1_12") (pintype "output"))
    )
    (net (code "217") (name "~{LAST_UNIT}") (class "Default")
      (node (ref "E12") (pin "8") (pinfunction "~{Q}_8") (pintype "output"))
      (node (ref "E2") (pin "3") (pinfunction "I0_3") (pintype "input"))
    )
    (net (code "218") (name "~{MD3}") (class "Default")
      (node (ref "E10") (pin "7") (pinfunction "I1_7") (pintype "input"))
      (node (ref "U$1") (pin "AP1") (pinfunction "1_AP1") (pintype "bidirectional"))
    )
    (net (code "219") (name "~{MD4}") (class "Default")
      (node (ref "E23") (pin "12") (pinfunction "I1_12") (pintype "input"))
      (node (ref "U$1") (pin "BK1") (pinfunction "1_BK1") (pintype "bidirectional"))
    )
    (net (code "220") (name "~{MD5}") (class "Default")
      (node (ref "E23") (pin "9") (pinfunction "I0_9") (pintype "input"))
      (node (ref "U$1") (pin "BL1") (pinfunction "1_BL1") (pintype "bidirectional"))
    )
    (net (code "221") (name "~{MD6}") (class "Default")
      (node (ref "E23") (pin "4") (pinfunction "I0_4") (pintype "input"))
      (node (ref "E24") (pin "5") (pinfunction "I1_5") (pintype "input"))
      (node (ref "U$1") (pin "BM1") (pinfunction "1_BM1") (pintype "bidirectional"))
    )
    (net (code "222") (name "~{MD7}") (class "Default")
      (node (ref "E23") (pin "7") (pinfunction "I1_7") (pintype "input"))
      (node (ref "E28") (pin "9") (pinfunction "I3_9") (pintype "input"))
      (node (ref "U$1") (pin "BP1") (pinfunction "1_BP1") (pintype "bidirectional"))
    )
    (net (code "223") (name "~{MD8}") (class "Default")
      (node (ref "E28") (pin "4") (pinfunction "I0_4") (pintype "input"))
      (node (ref "E35") (pin "7") (pinfunction "I1_7") (pintype "input"))
      (node (ref "U$1") (pin "DK1") (pinfunction "1_DK1") (pintype "bidirectional"))
    )
    (net (code "224") (name "~{MD9}") (class "Default")
      (node (ref "E35") (pin "4") (pinfunction "I0_4") (pintype "input"))
      (node (ref "U$1") (pin "DL1") (pinfunction "1_DL1") (pintype "bidirectional"))
    )
    (net (code "225") (name "~{MD10}") (class "Default")
      (node (ref "E35") (pin "12") (pinfunction "I1_12") (pintype "input"))
      (node (ref "U$1") (pin "DM1") (pinfunction "1_DM1") (pintype "bidirectional"))
    )
    (net (code "226") (name "~{MD11}") (class "Default")
      (node (ref "E35") (pin "9") (pinfunction "I0_9") (pintype "input"))
      (node (ref "U$1") (pin "DP1") (pinfunction "1_DP1") (pintype "bidirectional"))
    )
    (net (code "227") (name "~{POWER_OK}") (class "Default")
      (node (ref "E10") (pin "3") (pinfunction "O_3") (pintype "output"))
      (node (ref "E25") (pin "8") (pinfunction "I0_8") (pintype "input"))
    )
    (net (code "228") (name "~{PRESET}") (class "Default")
      (node (ref "E2") (pin "6") (pinfunction "O_6") (pintype "output"))
      (node (ref "E3") (pin "1") (pinfunction "I0_1") (pintype "input"))
      (node (ref "E6") (pin "1") (pinfunction "I_1") (pintype "input"))
      (node (ref "E7") (pin "1") (pinfunction "CLR_1") (pintype "input"))
      (node (ref "E7") (pin "13") (pinfunction "CLR_13") (pintype "input"))
    )
    (net (code "229") (name "~{RX_ACTIVE}") (class "Default")
      (node (ref "E1") (pin "6") (pinfunction "~{Q}_6") (pintype "output"))
      (node (ref "E17") (pin "13") (pinfunction "I1_13") (pintype "input"))
      (node (ref "E2") (pin "4") (pinfunction "I1_4") (pintype "input"))
      (node (ref "E2") (pin "5") (pinfunction "I2_5") (pintype "input"))
    )
    (net (code "230") (name "~{RX_CLK}") (class "Default")
      (node (ref "E1") (pin "11") (pinfunction "CLK_11") (pintype "input"))
      (node (ref "E3") (pin "12") (pinfunction "I0_12") (pintype "input"))
      (node (ref "E3") (pin "6") (pinfunction "O_6") (pintype "output"))
      (node (ref "E6") (pin "9") (pinfunction "I_9") (pintype "input"))
    )
    (net (code "231") (name "~{RX_CLR}") (class "Default")
      (node (ref "E1") (pin "10") (pinfunction "PRE_10") (pintype "input"))
      (node (ref "E11") (pin "8") (pinfunction "O_8") (pintype "output"))
      (node (ref "E40") (pin "10") (pinfunction "PRE_10") (pintype "input"))
      (node (ref "E40") (pin "4") (pinfunction "PRE_4") (pintype "input"))
      (node (ref "E41") (pin "10") (pinfunction "PRE_10") (pintype "input"))
      (node (ref "E41") (pin "4") (pinfunction "PRE_4") (pintype "input"))
      (node (ref "E51") (pin "10") (pinfunction "PRE_10") (pintype "input"))
      (node (ref "E51") (pin "4") (pinfunction "PRE_4") (pintype "input"))
      (node (ref "E52") (pin "10") (pinfunction "PRE_10") (pintype "input"))
      (node (ref "E52") (pin "4") (pinfunction "PRE_4") (pintype "input"))
    )
    (net (code "232") (name "~{RX_FLAG}") (class "Default")
      (node (ref "E17") (pin "4") (pinfunction "I0_4") (pintype "input"))
      (node (ref "E26") (pin "5") (pinfunction "I0_5") (pintype "input"))
      (node (ref "E42") (pin "8") (pinfunction "~{Q}_8") (pintype "output"))
    )
    (net (code "233") (name "~{SET_RR}") (class "Default")
      (node (ref "E30") (pin "10") (pinfunction "I1_10") (pintype "input"))
      (node (ref "E30") (pin "11") (pinfunction "O_11") (pintype "output"))
      (node (ref "E46") (pin "10") (pinfunction "PRE_10") (pintype "input"))
    )
    (net (code "234") (name "~{SKIP}") (class "Default")
      (node (ref "E33") (pin "1") (pinfunction "O_1") (pintype "open_collector"))
      (node (ref "E33") (pin "10") (pinfunction "O_10") (pintype "open_collector"))
      (node (ref "E33") (pin "13") (pinfunction "O_13") (pintype "open_collector"))
      (node (ref "U$1") (pin "CS1") (pinfunction "1_CS1") (pintype "bidirectional"))
    )
    (net (code "235") (name "~{STOP1}") (class "Default")
      (node (ref "E15") (pin "6") (pinfunction "~{Q}_6") (pintype "output"))
      (node (ref "STOP") (pin "3") (pinfunction "3_3") (pintype "passive"))
    )
    (net (code "236") (name "~{STOP2}") (class "Default")
      (node (ref "E19") (pin "6") (pinfunction "~{Q}_6") (pintype "output"))
      (node (ref "STOP") (pin "1") (pinfunction "1_1") (pintype "passive"))
      (node (ref "STOP2") (pin "2") (pinfunction "2_2") (pintype "passive"))
    )
    (net (code "237") (name "~{TCF}") (class "Default")
      (node (ref "E29") (pin "2") (pinfunction "I1_2") (pintype "input"))
      (node (ref "E38") (pin "11") (pinfunction "2_11") (pintype "output"))
    )
    (net (code "238") (name "~{TFLNOW}") (class "Default")
      (node (ref "E21") (pin "10") (pinfunction "PRE_10") (pintype "input"))
      (node (ref "E22") (pin "4") (pinfunction "O_4") (pintype "output"))
    )
    (net (code "239") (name "~{TFL}") (class "Default")
      (node (ref "E26") (pin "8") (pinfunction "I0_8") (pintype "input"))
      (node (ref "E38") (pin "13") (pinfunction "0_13") (pintype "output"))
    )
    (net (code "240") (name "~{TLS}") (class "Default")
      (node (ref "E29") (pin "1") (pinfunction "I0_1") (pintype "input"))
      (node (ref "E29") (pin "5") (pinfunction "I1_5") (pintype "input"))
      (node (ref "E38") (pin "4") (pinfunction "6_4") (pintype "output"))
    )
    (net (code "241") (name "~{TP3}") (class "Default")
      (node (ref "E22") (pin "2") (pinfunction "O_2") (pintype "output"))
      (node (ref "E26") (pin "11") (pinfunction "I0_11") (pintype "input"))
      (node (ref "E26") (pin "3") (pinfunction "I1_3") (pintype "input"))
      (node (ref "E26") (pin "9") (pinfunction "I1_9") (pintype "input"))
    )
    (net (code "242") (name "~{TPCNOW}") (class "Default")
      (node (ref "E32") (pin "13") (pinfunction "O_13") (pintype "open_collector"))
      (node (ref "E42") (pin "4") (pinfunction "PRE_4") (pintype "input"))
      (node (ref "E43") (pin "10") (pinfunction "I1_10") (pintype "input"))
      (node (ref "E43") (pin "11") (pinfunction "I0_11") (pintype "input"))
      (node (ref "E43") (pin "5") (pinfunction "I1_5") (pintype "input"))
      (node (ref "E43") (pin "7") (pinfunction "I1_7") (pintype "input"))
      (node (ref "E47") (pin "10") (pinfunction "I1_10") (pintype "input"))
      (node (ref "E47") (pin "11") (pinfunction "I0_11") (pintype "input"))
      (node (ref "E47") (pin "5") (pinfunction "I1_5") (pintype "input"))
      (node (ref "E47") (pin "7") (pinfunction "I1_7") (pintype "input"))
      (node (ref "R20") (pin "1") (pinfunction "1_1") (pintype "passive"))
    )
    (net (code "243") (name "~{TPC}") (class "Default")
      (node (ref "E29") (pin "4") (pinfunction "I0_4") (pintype "input"))
      (node (ref "E38") (pin "9") (pinfunction "4_9") (pintype "output"))
    )
    (net (code "244") (name "~{TSF}") (class "Default")
      (node (ref "E25") (pin "2") (pinfunction "I0_2") (pintype "input"))
      (node (ref "E38") (pin "12") (pinfunction "1_12") (pintype "output"))
    )
    (net (code "245") (name "~{TSK}") (class "Default")
      (node (ref "E25") (pin "6") (pinfunction "I1_6") (pintype "input"))
      (node (ref "E38") (pin "3") (pinfunction "5_3") (pintype "output"))
    )
    (net (code "246") (name "~{TX_BUSY}") (class "Default")
      (node (ref "E16") (pin "1") (pinfunction "I0_1") (pintype "input"))
      (node (ref "E21") (pin "12") (pinfunction "D_12") (pintype "input"))
      (node (ref "E22") (pin "10") (pinfunction "O_10") (pintype "output"))
    )
    (net (code "247") (name "~{TX_FLAG}") (class "Default")
      (node (ref "E17") (pin "5") (pinfunction "I1_5") (pintype "input"))
      (node (ref "E21") (pin "8") (pinfunction "~{Q}_8") (pintype "output"))
      (node (ref "E25") (pin "3") (pinfunction "I1_3") (pintype "input"))
    )
    (net (code "248") (name "~{XMIT_ACTIVE}") (class "Default")
      (node (ref "E15") (pin "8") (pinfunction "~{Q}_8") (pintype "output"))
      (node (ref "E6") (pin "11") (pinfunction "I_11") (pintype "input"))
    )
  )
)
